# 3-CPU_SIGNAL.net
KiCad netlist of a schematic drawn in Altium Designer
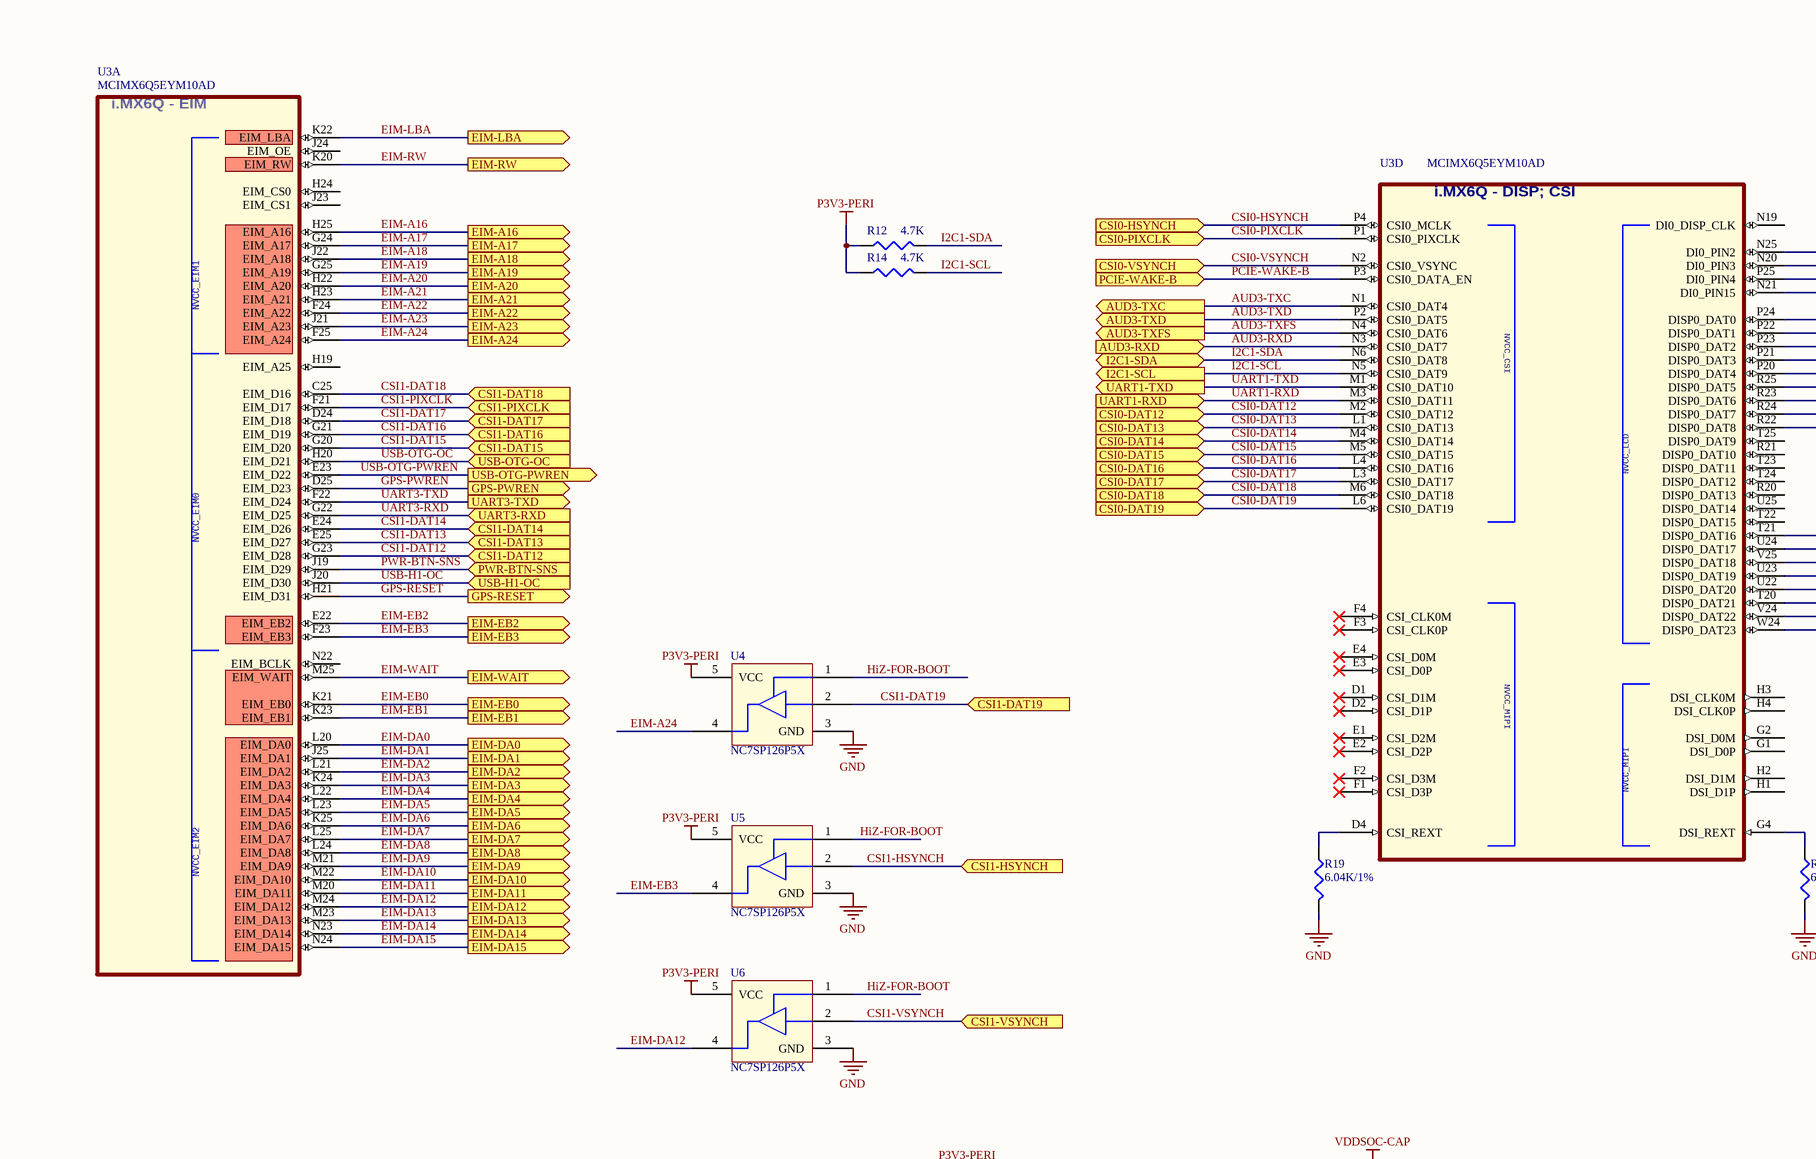
[diagram p0: 3-CPU_SIGNAL.SchDoc, top left]
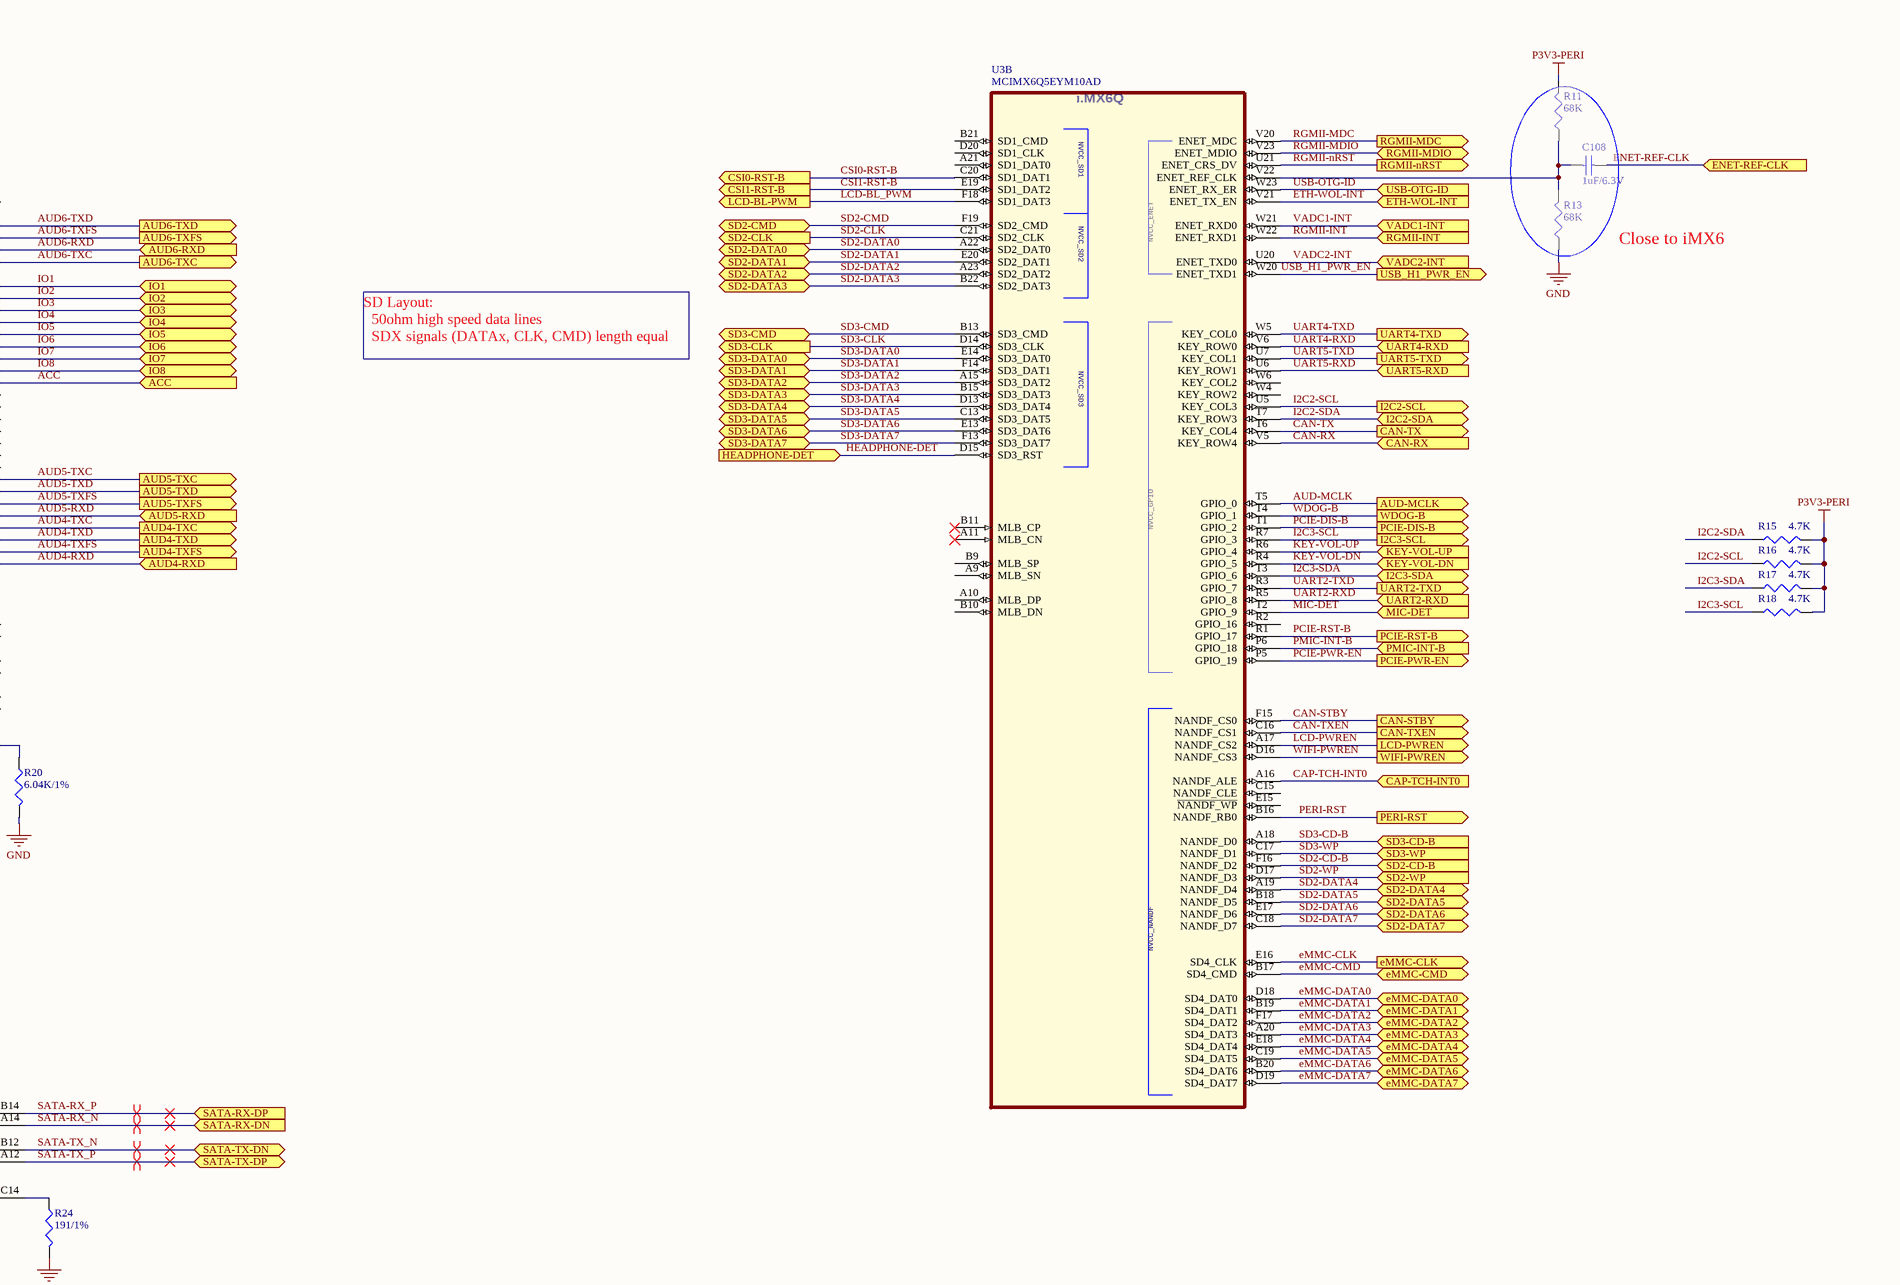
[diagram p1: 3-CPU_SIGNAL.SchDoc, top right]
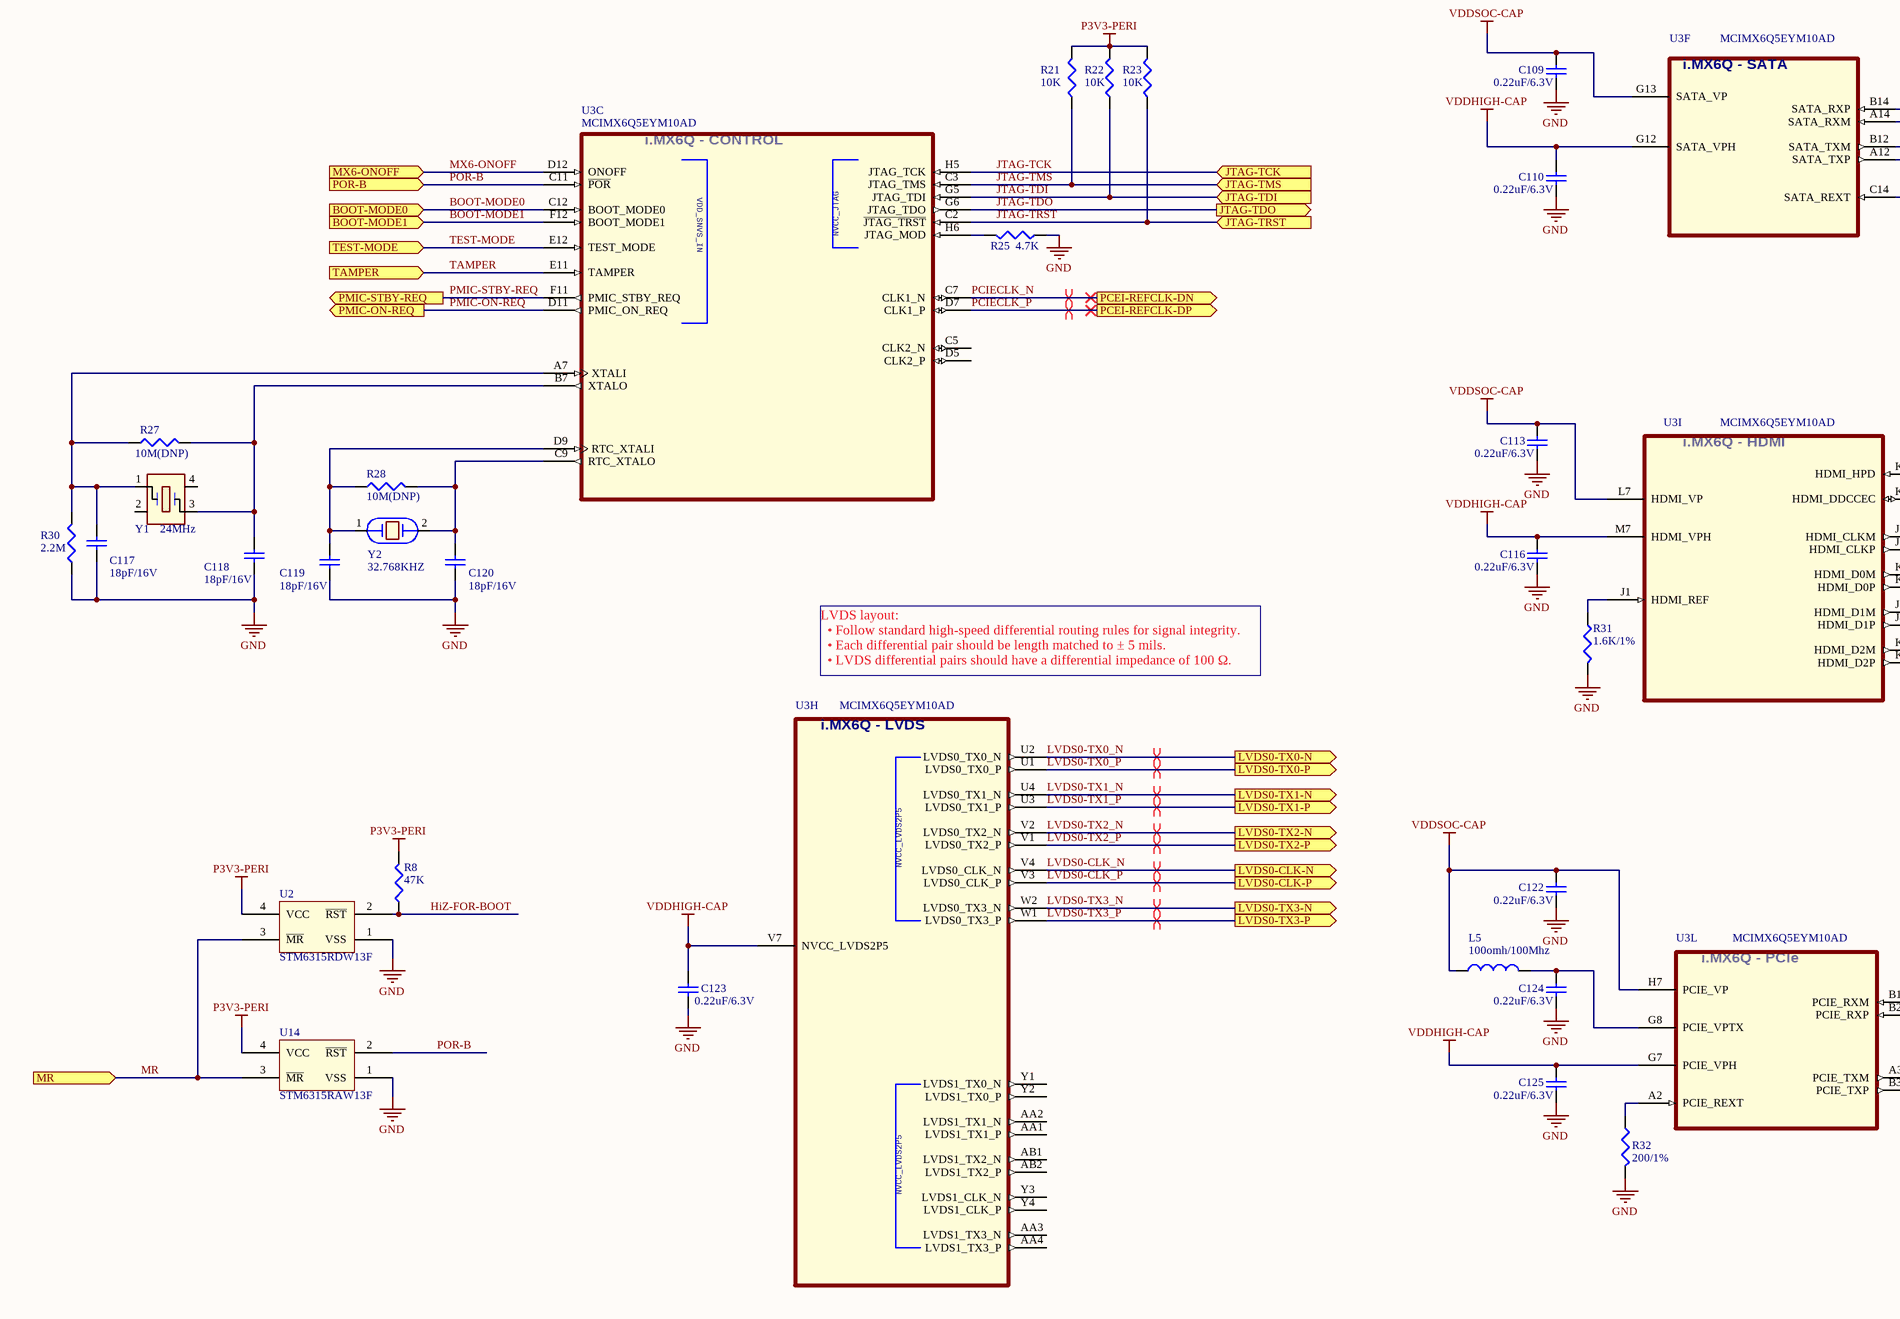
[diagram p2: 3-CPU_SIGNAL.SchDoc, bottom left]
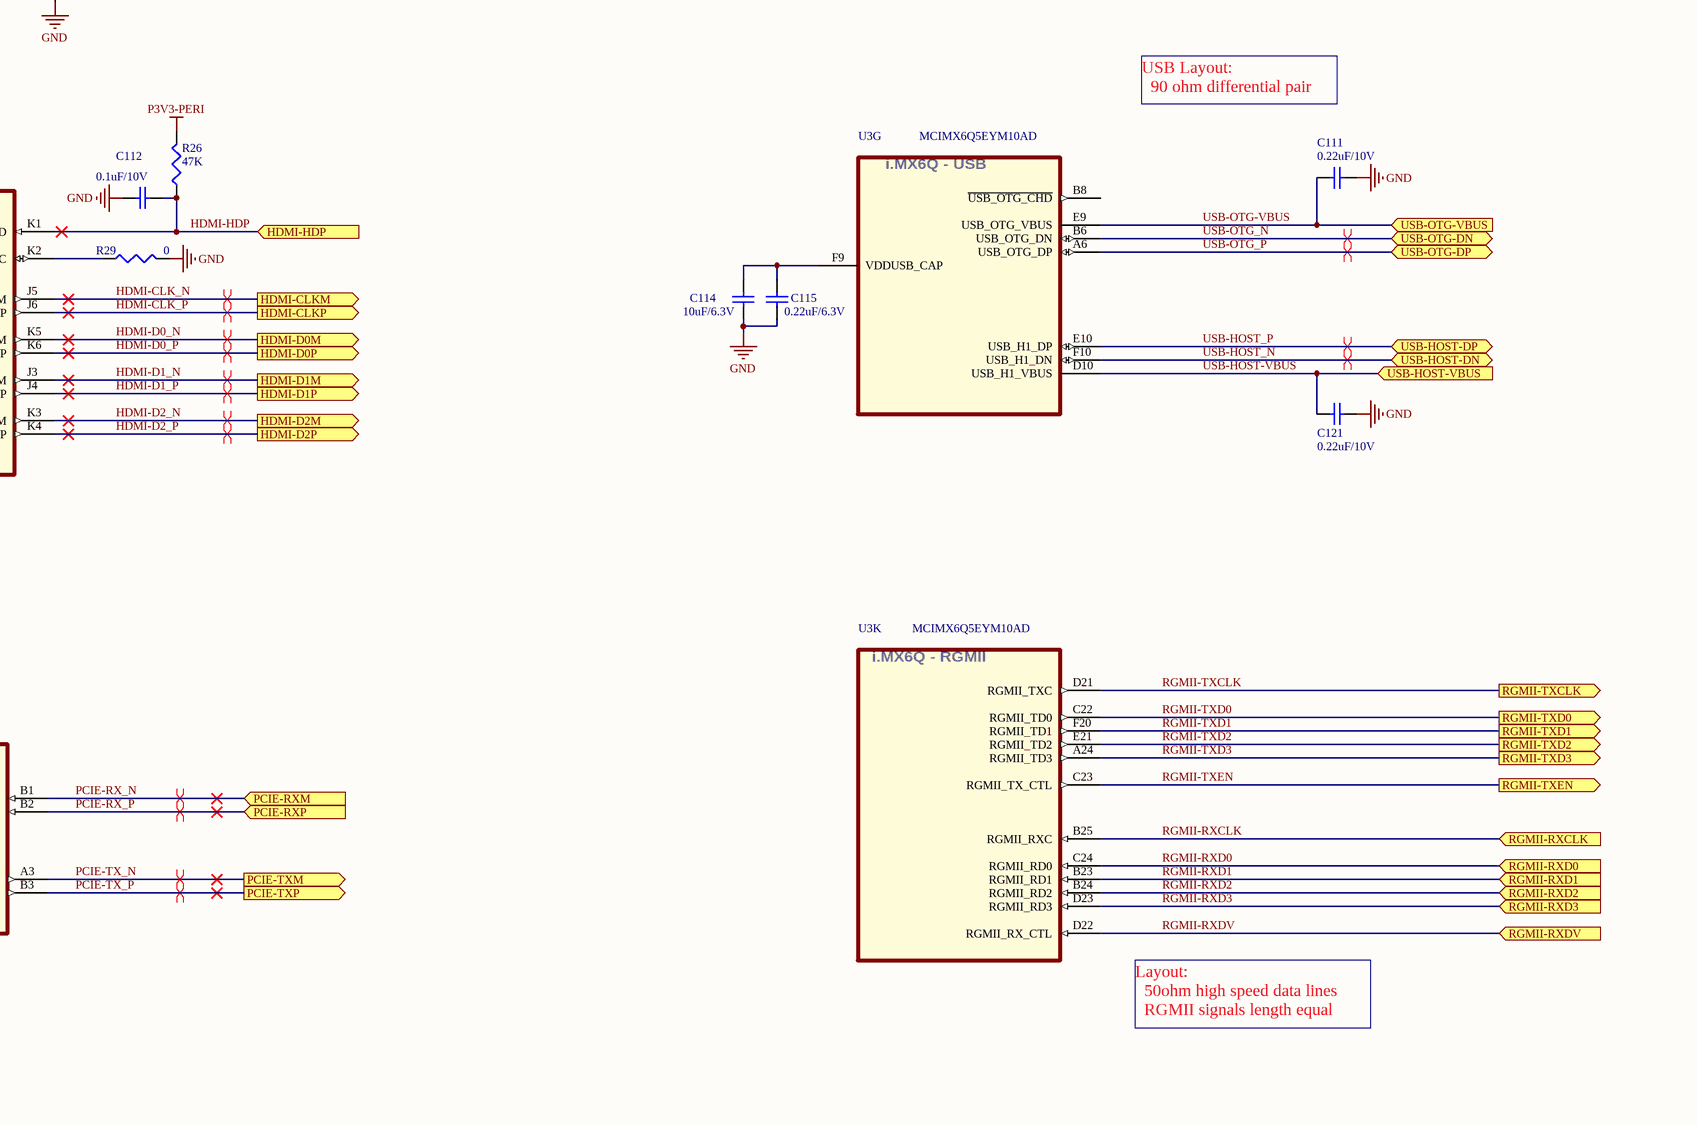
[diagram p3: 3-CPU_SIGNAL.SchDoc, bottom right]

(export (version "E")
  (design (tool "Eeschema 10.0.6"))
  (components
    (comp (ref "C108")
      (value "1uF/6.3V")
      (footprint "0402_CC")
      (description "Capacitor")
      (fields (field (name "PUBLISHER") "Altium Limited"))
      (libsource (lib "Miscellaneous Devices") (part "Cap"))
    )
    (comp (ref "C109")
      (value "0.22uF/6.3V")
      (footprint "0201_CC")
      (description "Capacitor")
      (fields (field (name "PUBLISHER") "Altium Limited"))
      (libsource (lib "Miscellaneous Devices") (part "Cap"))
    )
    (comp (ref "C110")
      (value "0.22uF/6.3V")
      (footprint "0201_CC")
      (description "Capacitor")
      (fields (field (name "PUBLISHER") "Altium Limited"))
      (libsource (lib "Miscellaneous Devices") (part "Cap"))
    )
    (comp (ref "C111")
      (value "0.22uF/10V")
      (footprint "0402_CC")
      (description "Capacitor")
      (fields (field (name "PUBLISHER") "Altium Limited"))
      (libsource (lib "Miscellaneous Devices") (part "Cap"))
    )
    (comp (ref "C112")
      (value "0.1uF/10V")
      (footprint "0402_CC")
      (description "Capacitor")
      (fields (field (name "PUBLISHER") "Altium Limited"))
      (libsource (lib "Miscellaneous Devices") (part "Cap"))
    )
    (comp (ref "C113")
      (value "0.22uF/6.3V")
      (footprint "0201_CC")
      (description "Capacitor")
      (fields (field (name "PUBLISHER") "Altium Limited"))
      (libsource (lib "Miscellaneous Devices") (part "Cap"))
    )
    (comp (ref "C114")
      (value "10uF/6.3V")
      (footprint "0805_CC")
      (description "Capacitor")
      (fields (field (name "PUBLISHER") "Altium Limited"))
      (libsource (lib "Miscellaneous Devices") (part "Cap"))
    )
    (comp (ref "C115")
      (value "0.22uF/6.3V")
      (footprint "0201_CC")
      (description "Capacitor")
      (fields (field (name "PUBLISHER") "Altium Limited"))
      (libsource (lib "Miscellaneous Devices") (part "Cap"))
    )
    (comp (ref "C116")
      (value "0.22uF/6.3V")
      (footprint "0201_CC")
      (description "Capacitor")
      (fields (field (name "PUBLISHER") "Altium Limited"))
      (libsource (lib "Miscellaneous Devices") (part "Cap"))
    )
    (comp (ref "C117")
      (value "18pF/16V")
      (footprint "0402_CC")
      (description "Capacitor")
      (fields (field (name "PUBLISHER") "Altium Limited"))
      (libsource (lib "Miscellaneous Devices") (part "Cap"))
    )
    (comp (ref "C118")
      (value "18pF/16V")
      (footprint "0402_CC")
      (description "Capacitor")
      (fields (field (name "PUBLISHER") "Altium Limited"))
      (libsource (lib "Miscellaneous Devices") (part "Cap"))
    )
    (comp (ref "C119")
      (value "18pF/16V")
      (footprint "0402_CC")
      (description "Capacitor")
      (fields (field (name "PUBLISHER") "Altium Limited"))
      (libsource (lib "Miscellaneous Devices") (part "Cap"))
    )
    (comp (ref "C120")
      (value "18pF/16V")
      (footprint "0402_CC")
      (description "Capacitor")
      (fields (field (name "PUBLISHER") "Altium Limited"))
      (libsource (lib "Miscellaneous Devices") (part "Cap"))
    )
    (comp (ref "C121")
      (value "0.22uF/10V")
      (footprint "0402_CC")
      (description "Capacitor")
      (fields (field (name "PUBLISHER") "Altium Limited"))
      (libsource (lib "Miscellaneous Devices") (part "Cap"))
    )
    (comp (ref "C122")
      (value "0.22uF/6.3V")
      (footprint "0201_CC")
      (description "Capacitor")
      (fields (field (name "PUBLISHER") "Altium Limited"))
      (libsource (lib "Miscellaneous Devices") (part "Cap"))
    )
    (comp (ref "C123")
      (value "0.22uF/6.3V")
      (footprint "0201_CC")
      (description "Capacitor")
      (fields (field (name "PUBLISHER") "Altium Limited"))
      (libsource (lib "Miscellaneous Devices") (part "Cap"))
    )
    (comp (ref "C124")
      (value "0.22uF/6.3V")
      (footprint "0201_CC")
      (description "Capacitor")
      (fields (field (name "PUBLISHER") "Altium Limited"))
      (libsource (lib "Miscellaneous Devices") (part "Cap"))
    )
    (comp (ref "C125")
      (value "0.22uF/6.3V")
      (footprint "0201_CC")
      (description "Capacitor")
      (fields (field (name "PUBLISHER") "Altium Limited"))
      (libsource (lib "Miscellaneous Devices") (part "Cap"))
    )
    (comp (ref "L5")
      (value "100omh/100Mhz")
      (footprint "0603_CC")
      (description "Inductor")
      (fields (field (name "PUBLISHER") "Altium Limited"))
      (libsource (lib "Miscellaneous Devices") (part "Inductor"))
    )
    (comp (ref "R8")
      (value "47K")
      (footprint "0402_CC")
      (description "Resistor")
      (fields (field (name "PUBLISHER") "Altium Limited"))
      (libsource (lib "Miscellaneous Devices") (part "Res3"))
    )
    (comp (ref "R11")
      (value "68K")
      (footprint "0402_CC")
      (description "Resistor")
      (fields (field (name "PUBLISHER") "Altium Limited"))
      (libsource (lib "Miscellaneous Devices") (part "Res3"))
    )
    (comp (ref "R12")
      (value "4.7K")
      (footprint "0402_CC")
      (description "Resistor")
      (fields (field (name "PUBLISHER") "Altium Limited"))
      (libsource (lib "Miscellaneous Devices") (part "Res3"))
    )
    (comp (ref "R13")
      (value "68K")
      (footprint "0402_CC")
      (description "Resistor")
      (fields (field (name "PUBLISHER") "Altium Limited"))
      (libsource (lib "Miscellaneous Devices") (part "Res3"))
    )
    (comp (ref "R14")
      (value "4.7K")
      (footprint "0402_CC")
      (description "Resistor")
      (fields (field (name "PUBLISHER") "Altium Limited"))
      (libsource (lib "Miscellaneous Devices") (part "Res3"))
    )
    (comp (ref "R15")
      (value "4.7K")
      (footprint "0402_CC")
      (description "Resistor")
      (fields (field (name "PUBLISHER") "Altium Limited"))
      (libsource (lib "Miscellaneous Devices") (part "Res3"))
    )
    (comp (ref "R16")
      (value "4.7K")
      (footprint "0402_CC")
      (description "Resistor")
      (fields (field (name "PUBLISHER") "Altium Limited"))
      (libsource (lib "Miscellaneous Devices") (part "Res3"))
    )
    (comp (ref "R17")
      (value "4.7K")
      (footprint "0402_CC")
      (description "Resistor")
      (fields (field (name "PUBLISHER") "Altium Limited"))
      (libsource (lib "Miscellaneous Devices") (part "Res3"))
    )
    (comp (ref "R18")
      (value "4.7K")
      (footprint "0402_CC")
      (description "Resistor")
      (fields (field (name "PUBLISHER") "Altium Limited"))
      (libsource (lib "Miscellaneous Devices") (part "Res3"))
    )
    (comp (ref "R19")
      (value "6.04K/1%")
      (footprint "0402_CC")
      (description "Resistor")
      (fields (field (name "PUBLISHER") "Altium Limited"))
      (libsource (lib "Miscellaneous Devices") (part "Res3"))
    )
    (comp (ref "R20")
      (value "6.04K/1%")
      (footprint "0402_CC")
      (description "Resistor")
      (fields (field (name "PUBLISHER") "Altium Limited"))
      (libsource (lib "Miscellaneous Devices") (part "Res3"))
    )
    (comp (ref "R21")
      (value "10K")
      (footprint "0402_CC")
      (description "Resistor")
      (fields (field (name "PUBLISHER") "Altium Limited"))
      (libsource (lib "Miscellaneous Devices") (part "Res3"))
    )
    (comp (ref "R22")
      (value "10K")
      (footprint "0402_CC")
      (description "Resistor")
      (fields (field (name "PUBLISHER") "Altium Limited"))
      (libsource (lib "Miscellaneous Devices") (part "Res3"))
    )
    (comp (ref "R23")
      (value "10K")
      (footprint "0402_CC")
      (description "Resistor")
      (fields (field (name "PUBLISHER") "Altium Limited"))
      (libsource (lib "Miscellaneous Devices") (part "Res3"))
    )
    (comp (ref "R24")
      (value "191/1%")
      (footprint "0402_CC")
      (description "Resistor")
      (fields (field (name "PUBLISHER") "Altium Limited"))
      (libsource (lib "Miscellaneous Devices") (part "Res3"))
    )
    (comp (ref "R25")
      (value "4.7K")
      (footprint "0402_CC")
      (description "Resistor")
      (fields (field (name "PUBLISHER") "Altium Limited"))
      (libsource (lib "Miscellaneous Devices") (part "Res3"))
    )
    (comp (ref "R26")
      (value "47K")
      (footprint "0402_CC")
      (description "Resistor")
      (fields (field (name "PUBLISHER") "Altium Limited"))
      (libsource (lib "Miscellaneous Devices") (part "Res3"))
    )
    (comp (ref "R27")
      (value "10M(DNP)")
      (footprint "0402_CC")
      (description "Resistor")
      (fields (field (name "PUBLISHER") "Altium Limited"))
      (libsource (lib "Miscellaneous Devices") (part "Res3"))
    )
    (comp (ref "R28")
      (value "10M(DNP)")
      (footprint "0402_CC")
      (description "Resistor")
      (fields (field (name "PUBLISHER") "Altium Limited"))
      (libsource (lib "Miscellaneous Devices") (part "Res3"))
    )
    (comp (ref "R29")
      (value "0")
      (footprint "0402_CC")
      (description "Resistor")
      (fields (field (name "PUBLISHER") "Altium Limited"))
      (libsource (lib "Miscellaneous Devices") (part "Res3"))
    )
    (comp (ref "R30")
      (value "2.2M")
      (footprint "0402_CC")
      (description "Resistor")
      (fields (field (name "PUBLISHER") "Altium Limited"))
      (libsource (lib "Miscellaneous Devices") (part "Res3"))
    )
    (comp (ref "R31")
      (value "1.6K/1%")
      (footprint "0402_CC")
      (description "Resistor")
      (fields (field (name "PUBLISHER") "Altium Limited"))
      (libsource (lib "Miscellaneous Devices") (part "Res3"))
    )
    (comp (ref "R32")
      (value "200/1%")
      (footprint "0402_CC")
      (description "Resistor")
      (fields (field (name "PUBLISHER") "Altium Limited"))
      (libsource (lib "Miscellaneous Devices") (part "Res3"))
    )
    (comp (ref "U2")
      (value "STM6315RDW13F")
      (footprint "SOT143-4")
      (libsource (lib "Schlib") (part "STM6315"))
    )
    (comp (ref "U3")
      (value "MCIMX6Q5EYM10AD")
      (footprint "FCPBGA")
      (description "IC MCU MX6QUAD ARM CORTEX-A9 FCPBGA624")
      (libsource (lib "*") (part "PCIMX6Q6VV1A"))
    )
    (comp (ref "U4") (value "NC7SP126P5X") (footprint "SC70") (libsource (lib "Schlib") (part "NC7SP126P5X")))
    (comp (ref "U5") (value "NC7SP126P5X") (footprint "SC70") (libsource (lib "Schlib") (part "NC7SP126P5X")))
    (comp (ref "U6") (value "NC7SP126P5X") (footprint "SC70") (libsource (lib "Schlib") (part "NC7SP126P5X")))
    (comp (ref "U14")
      (value "STM6315RAW13F")
      (footprint "SOT143-4")
      (libsource (lib "Schlib") (part "STM6315"))
    )
    (comp (ref "Y1")
      (value "24MHz")
      (footprint "XTAL4_SX_3225")
      (description "XTAL 24MHZ -- 3.2X2.5MM SMT")
      (libsource (lib "*") (part "XTAL_13Y_A"))
    )
    (comp (ref "Y2")
      (value "32.768KHZ")
      (footprint "XTAL2-3P2X1P5-SM")
      (description "XTAL 32.768KHZ 12.5PF 20PPM 3.2X1.5MM SMT")
      (libsource (lib "*") (part "XTAL"))
    )
  )
  (nets
    (net (code "1") (name "/ACC") (class "Default")
      (node (ref "U3") (pin "R22") (pinfunction "DISP0_DAT8_R22") (pintype "bidirectional"))
    )
    (net (code "2") (name "/AUD-MCLK") (class "Default")
      (node (ref "U3") (pin "T5") (pinfunction "GPIO_0_T5") (pintype "bidirectional"))
    )
    (net (code "3") (name "/AUD3-RXD") (class "Default")
      (node (ref "U3") (pin "N3") (pinfunction "CSI0_DAT7_N3") (pintype "bidirectional"))
    )
    (net (code "4") (name "/AUD3-TXC") (class "Default")
      (node (ref "U3") (pin "N1") (pinfunction "CSI0_DAT4_N1") (pintype "bidirectional"))
    )
    (net (code "5") (name "/AUD3-TXD") (class "Default")
      (node (ref "U3") (pin "P2") (pinfunction "CSI0_DAT5_P2") (pintype "bidirectional"))
    )
    (net (code "6") (name "/AUD3-TXFS") (class "Default")
      (node (ref "U3") (pin "N4") (pinfunction "CSI0_DAT6_N4") (pintype "bidirectional"))
    )
    (net (code "7") (name "/AUD4-RXD") (class "Default")
      (node (ref "U3") (pin "W24") (pinfunction "DISP0_DAT23_W24") (pintype "bidirectional"))
    )
    (net (code "8") (name "/AUD4-TXC") (class "Default")
      (node (ref "U3") (pin "U22") (pinfunction "DISP0_DAT20_U22") (pintype "bidirectional"))
    )
    (net (code "9") (name "/AUD4-TXD") (class "Default")
      (node (ref "U3") (pin "T20") (pinfunction "DISP0_DAT21_T20") (pintype "bidirectional"))
    )
    (net (code "10") (name "/AUD4-TXFS") (class "Default")
      (node (ref "U3") (pin "V24") (pinfunction "DISP0_DAT22_V24") (pintype "bidirectional"))
    )
    (net (code "11") (name "/AUD5-RXD") (class "Default")
      (node (ref "U3") (pin "U23") (pinfunction "DISP0_DAT19_U23") (pintype "bidirectional"))
    )
    (net (code "12") (name "/AUD5-TXC") (class "Default")
      (node (ref "U3") (pin "T21") (pinfunction "DISP0_DAT16_T21") (pintype "bidirectional"))
    )
    (net (code "13") (name "/AUD5-TXD") (class "Default")
      (node (ref "U3") (pin "U24") (pinfunction "DISP0_DAT17_U24") (pintype "bidirectional"))
    )
    (net (code "14") (name "/AUD5-TXFS") (class "Default")
      (node (ref "U3") (pin "V25") (pinfunction "DISP0_DAT18_V25") (pintype "bidirectional"))
    )
    (net (code "15") (name "/AUD6-RXD") (class "Default")
      (node (ref "U3") (pin "P25") (pinfunction "DI0_PIN4_P25") (pintype "bidirectional"))
    )
    (net (code "16") (name "/AUD6-TXC") (class "Default")
      (node (ref "U3") (pin "N21") (pinfunction "DI0_PIN15_N21") (pintype "bidirectional"))
    )
    (net (code "17") (name "/AUD6-TXD") (class "Default")
      (node (ref "U3") (pin "N25") (pinfunction "DI0_PIN2_N25") (pintype "bidirectional"))
    )
    (net (code "18") (name "/AUD6-TXFS") (class "Default")
      (node (ref "U3") (pin "N20") (pinfunction "DI0_PIN3_N20") (pintype "bidirectional"))
    )
    (net (code "19") (name "/BOOT-MODE0") (class "Default")
      (node (ref "U3") (pin "C12") (pinfunction "BOOT_MODE0_C12") (pintype "input"))
    )
    (net (code "20") (name "/BOOT-MODE1") (class "Default")
      (node (ref "U3") (pin "F12") (pinfunction "BOOT_MODE1_F12") (pintype "input"))
    )
    (net (code "21") (name "/CAN-RX") (class "Default")
      (node (ref "U3") (pin "V5") (pinfunction "KEY_ROW4_V5") (pintype "bidirectional"))
    )
    (net (code "22") (name "/CAN-STBY") (class "Default")
      (node (ref "U3") (pin "F15") (pinfunction "NANDF_CS0_F15") (pintype "bidirectional"))
    )
    (net (code "23") (name "/CAN-TX") (class "Default")
      (node (ref "U3") (pin "T6") (pinfunction "KEY_COL4_T6") (pintype "bidirectional"))
    )
    (net (code "24") (name "/CAN-TXEN") (class "Default")
      (node (ref "U3") (pin "C16") (pinfunction "NANDF_CS1_C16") (pintype "bidirectional"))
    )
    (net (code "25") (name "/CAP-TCH-INT0") (class "Default")
      (node (ref "U3") (pin "A16") (pinfunction "NANDF_ALE_A16") (pintype "bidirectional"))
    )
    (net (code "26") (name "/CSI0-DAT12") (class "Default")
      (node (ref "U3") (pin "M2") (pinfunction "CSI0_DAT12_M2") (pintype "bidirectional"))
    )
    (net (code "27") (name "/CSI0-DAT13") (class "Default")
      (node (ref "U3") (pin "L1") (pinfunction "CSI0_DAT13_L1") (pintype "bidirectional"))
    )
    (net (code "28") (name "/CSI0-DAT14") (class "Default")
      (node (ref "U3") (pin "M4") (pinfunction "CSI0_DAT14_M4") (pintype "bidirectional"))
    )
    (net (code "29") (name "/CSI0-DAT15") (class "Default")
      (node (ref "U3") (pin "M5") (pinfunction "CSI0_DAT15_M5") (pintype "bidirectional"))
    )
    (net (code "30") (name "/CSI0-DAT16") (class "Default")
      (node (ref "U3") (pin "L4") (pinfunction "CSI0_DAT16_L4") (pintype "bidirectional"))
    )
    (net (code "31") (name "/CSI0-DAT17") (class "Default")
      (node (ref "U3") (pin "L3") (pinfunction "CSI0_DAT17_L3") (pintype "bidirectional"))
    )
    (net (code "32") (name "/CSI0-DAT18") (class "Default")
      (node (ref "U3") (pin "M6") (pinfunction "CSI0_DAT18_M6") (pintype "bidirectional"))
    )
    (net (code "33") (name "/CSI0-DAT19") (class "Default")
      (node (ref "U3") (pin "L6") (pinfunction "CSI0_DAT19_L6") (pintype "bidirectional"))
    )
    (net (code "34") (name "/CSI0-HSYNCH") (class "Default")
      (node (ref "U3") (pin "P4") (pinfunction "CSI0_MCLK_P4") (pintype "bidirectional"))
    )
    (net (code "35") (name "/CSI0-PIXCLK") (class "Default")
      (node (ref "U3") (pin "P1") (pinfunction "CSI0_PIXCLK_P1") (pintype "bidirectional"))
    )
    (net (code "36") (name "/CSI0-RST-B") (class "Default")
      (node (ref "U3") (pin "C20") (pinfunction "SD1_DAT1_C20") (pintype "bidirectional"))
    )
    (net (code "37") (name "/CSI0-VSYNCH") (class "Default")
      (node (ref "U3") (pin "N2") (pinfunction "CSI0_VSYNC_N2") (pintype "bidirectional"))
    )
    (net (code "38") (name "/CSI1-DAT12") (class "Default")
      (node (ref "U3") (pin "G23") (pinfunction "EIM_D28_G23") (pintype "bidirectional"))
    )
    (net (code "39") (name "/CSI1-DAT13") (class "Default")
      (node (ref "U3") (pin "E25") (pinfunction "EIM_D27_E25") (pintype "bidirectional"))
    )
    (net (code "40") (name "/CSI1-DAT14") (class "Default")
      (node (ref "U3") (pin "E24") (pinfunction "EIM_D26_E24") (pintype "bidirectional"))
    )
    (net (code "41") (name "/CSI1-DAT15") (class "Default")
      (node (ref "U3") (pin "G20") (pinfunction "EIM_D20_G20") (pintype "bidirectional"))
    )
    (net (code "42") (name "/CSI1-DAT16") (class "Default")
      (node (ref "U3") (pin "G21") (pinfunction "EIM_D19_G21") (pintype "bidirectional"))
    )
    (net (code "43") (name "/CSI1-DAT17") (class "Default")
      (node (ref "U3") (pin "D24") (pinfunction "EIM_D18_D24") (pintype "bidirectional"))
    )
    (net (code "44") (name "/CSI1-DAT18") (class "Default")
      (node (ref "U3") (pin "C25") (pinfunction "EIM_D16_C25") (pintype "bidirectional"))
    )
    (net (code "45") (name "/CSI1-DAT19") (class "Default")
      (node (ref "U4") (pin "2") (pinfunction "A_2") (pintype "passive"))
    )
    (net (code "46") (name "/CSI1-HSYNCH") (class "Default")
      (node (ref "U5") (pin "2") (pinfunction "A_2") (pintype "passive"))
    )
    (net (code "47") (name "/CSI1-PIXCLK") (class "Default")
      (node (ref "U3") (pin "F21") (pinfunction "EIM_D17_F21") (pintype "bidirectional"))
    )
    (net (code "48") (name "/CSI1-RST-B") (class "Default")
      (node (ref "U3") (pin "E19") (pinfunction "SD1_DAT2_E19") (pintype "bidirectional"))
    )
    (net (code "49") (name "/CSI1-VSYNCH") (class "Default")
      (node (ref "U6") (pin "2") (pinfunction "A_2") (pintype "passive"))
    )
    (net (code "50") (name "/EIM-A16") (class "Default")
      (node (ref "U3") (pin "H25") (pinfunction "EIM_A16_H25") (pintype "bidirectional"))
    )
    (net (code "51") (name "/EIM-A17") (class "Default")
      (node (ref "U3") (pin "G24") (pinfunction "EIM_A17_G24") (pintype "bidirectional"))
    )
    (net (code "52") (name "/EIM-A18") (class "Default")
      (node (ref "U3") (pin "J22") (pinfunction "EIM_A18_J22") (pintype "bidirectional"))
    )
    (net (code "53") (name "/EIM-A19") (class "Default")
      (node (ref "U3") (pin "G25") (pinfunction "EIM_A19_G25") (pintype "bidirectional"))
    )
    (net (code "54") (name "/EIM-A20") (class "Default")
      (node (ref "U3") (pin "H22") (pinfunction "EIM_A20_H22") (pintype "bidirectional"))
    )
    (net (code "55") (name "/EIM-A21") (class "Default")
      (node (ref "U3") (pin "H23") (pinfunction "EIM_A21_H23") (pintype "bidirectional"))
    )
    (net (code "56") (name "/EIM-A22") (class "Default")
      (node (ref "U3") (pin "F24") (pinfunction "EIM_A22_F24") (pintype "bidirectional"))
    )
    (net (code "57") (name "/EIM-A23") (class "Default")
      (node (ref "U3") (pin "J21") (pinfunction "EIM_A23_J21") (pintype "bidirectional"))
    )
    (net (code "58") (name "/EIM-A24") (class "Default")
      (node (ref "U3") (pin "F25") (pinfunction "EIM_A24_F25") (pintype "bidirectional"))
      (node (ref "U4") (pin "4") (pinfunction "Y_4") (pintype "passive"))
    )
    (net (code "59") (name "/EIM-DA0") (class "Default")
      (node (ref "U3") (pin "L20") (pinfunction "EIM_DA0_L20") (pintype "bidirectional"))
    )
    (net (code "60") (name "/EIM-DA1") (class "Default")
      (node (ref "U3") (pin "J25") (pinfunction "EIM_DA1_J25") (pintype "bidirectional"))
    )
    (net (code "61") (name "/EIM-DA2") (class "Default")
      (node (ref "U3") (pin "L21") (pinfunction "EIM_DA2_L21") (pintype "bidirectional"))
    )
    (net (code "62") (name "/EIM-DA3") (class "Default")
      (node (ref "U3") (pin "K24") (pinfunction "EIM_DA3_K24") (pintype "bidirectional"))
    )
    (net (code "63") (name "/EIM-DA4") (class "Default")
      (node (ref "U3") (pin "L22") (pinfunction "EIM_DA4_L22") (pintype "bidirectional"))
    )
    (net (code "64") (name "/EIM-DA5") (class "Default")
      (node (ref "U3") (pin "L23") (pinfunction "EIM_DA5_L23") (pintype "bidirectional"))
    )
    (net (code "65") (name "/EIM-DA6") (class "Default")
      (node (ref "U3") (pin "K25") (pinfunction "EIM_DA6_K25") (pintype "bidirectional"))
    )
    (net (code "66") (name "/EIM-DA7") (class "Default")
      (node (ref "U3") (pin "L25") (pinfunction "EIM_DA7_L25") (pintype "bidirectional"))
    )
    (net (code "67") (name "/EIM-DA8") (class "Default")
      (node (ref "U3") (pin "L24") (pinfunction "EIM_DA8_L24") (pintype "bidirectional"))
    )
    (net (code "68") (name "/EIM-DA9") (class "Default")
      (node (ref "U3") (pin "M21") (pinfunction "EIM_DA9_M21") (pintype "bidirectional"))
    )
    (net (code "69") (name "/EIM-DA10") (class "Default")
      (node (ref "U3") (pin "M22") (pinfunction "EIM_DA10_M22") (pintype "bidirectional"))
    )
    (net (code "70") (name "/EIM-DA11") (class "Default")
      (node (ref "U3") (pin "M20") (pinfunction "EIM_DA11_M20") (pintype "bidirectional"))
    )
    (net (code "71") (name "/EIM-DA12") (class "Default")
      (node (ref "U3") (pin "M24") (pinfunction "EIM_DA12_M24") (pintype "bidirectional"))
      (node (ref "U6") (pin "4") (pinfunction "Y_4") (pintype "passive"))
    )
    (net (code "72") (name "/EIM-DA13") (class "Default")
      (node (ref "U3") (pin "M23") (pinfunction "EIM_DA13_M23") (pintype "bidirectional"))
    )
    (net (code "73") (name "/EIM-DA14") (class "Default")
      (node (ref "U3") (pin "N23") (pinfunction "EIM_DA14_N23") (pintype "bidirectional"))
    )
    (net (code "74") (name "/EIM-DA15") (class "Default")
      (node (ref "U3") (pin "N24") (pinfunction "EIM_DA15_N24") (pintype "bidirectional"))
    )
    (net (code "75") (name "/EIM-EB0") (class "Default")
      (node (ref "U3") (pin "K21") (pinfunction "EIM_EB0_K21") (pintype "bidirectional"))
    )
    (net (code "76") (name "/EIM-EB1") (class "Default")
      (node (ref "U3") (pin "K23") (pinfunction "EIM_EB1_K23") (pintype "bidirectional"))
    )
    (net (code "77") (name "/EIM-EB2") (class "Default")
      (node (ref "U3") (pin "E22") (pinfunction "EIM_EB2_E22") (pintype "bidirectional"))
    )
    (net (code "78") (name "/EIM-EB3") (class "Default")
      (node (ref "U3") (pin "F23") (pinfunction "EIM_EB3_F23") (pintype "bidirectional"))
      (node (ref "U5") (pin "4") (pinfunction "Y_4") (pintype "passive"))
    )
    (net (code "79") (name "/EIM-LBA") (class "Default")
      (node (ref "U3") (pin "K22") (pinfunction "EIM_LBA_K22") (pintype "bidirectional"))
    )
    (net (code "80") (name "/EIM-RW") (class "Default")
      (node (ref "U3") (pin "K20") (pinfunction "EIM_RW_K20") (pintype "bidirectional"))
    )
    (net (code "81") (name "/EIM-WAIT") (class "Default")
      (node (ref "U3") (pin "M25") (pinfunction "EIM_WAIT_M25") (pintype "bidirectional"))
    )
    (net (code "82") (name "/ENET-REF-CLK") (class "Default")
      (node (ref "C108") (pin "2") (pinfunction "2_2") (pintype "passive"))
    )
    (net (code "83") (name "/ETH-WOL-INT") (class "Default")
      (node (ref "U3") (pin "V21") (pinfunction "ENET_TX_EN_V21") (pintype "bidirectional"))
    )
    (net (code "84") (name "/GPS-PWREN") (class "Default")
      (node (ref "U3") (pin "D25") (pinfunction "EIM_D23_D25") (pintype "bidirectional"))
    )
    (net (code "85") (name "/GPS-RESET") (class "Default")
      (node (ref "U3") (pin "H21") (pinfunction "EIM_D31_H21") (pintype "bidirectional"))
    )
    (net (code "86") (name "/HDMI-CLK_N") (class "Default")
      (node (ref "U3") (pin "J5") (pinfunction "HDMI_CLKM_J5") (pintype "output"))
    )
    (net (code "87") (name "/HDMI-CLK_P") (class "Default")
      (node (ref "U3") (pin "J6") (pinfunction "HDMI_CLKP_J6") (pintype "output"))
    )
    (net (code "88") (name "/HDMI-D0_N") (class "Default")
      (node (ref "U3") (pin "K5") (pinfunction "HDMI_D0M_K5") (pintype "output"))
    )
    (net (code "89") (name "/HDMI-D0_P") (class "Default")
      (node (ref "U3") (pin "K6") (pinfunction "HDMI_D0P_K6") (pintype "output"))
    )
    (net (code "90") (name "/HDMI-D1_N") (class "Default")
      (node (ref "U3") (pin "J3") (pinfunction "HDMI_D1M_J3") (pintype "output"))
    )
    (net (code "91") (name "/HDMI-D1_P") (class "Default")
      (node (ref "U3") (pin "J4") (pinfunction "HDMI_D1P_J4") (pintype "output"))
    )
    (net (code "92") (name "/HDMI-D2_N") (class "Default")
      (node (ref "U3") (pin "K3") (pinfunction "HDMI_D2M_K3") (pintype "output"))
    )
    (net (code "93") (name "/HDMI-D2_P") (class "Default")
      (node (ref "U3") (pin "K4") (pinfunction "HDMI_D2P_K4") (pintype "output"))
    )
    (net (code "94") (name "/HDMI-HDP") (class "Default")
      (node (ref "C112") (pin "2") (pinfunction "2_2") (pintype "passive"))
      (node (ref "R26") (pin "1") (pinfunction "1_1") (pintype "passive"))
      (node (ref "U3") (pin "K1") (pinfunction "HDMI_HPD_K1") (pintype "input"))
    )
    (net (code "95") (name "/HEADPHONE-DET") (class "Default")
      (node (ref "U3") (pin "D15") (pinfunction "SD3_RST_D15") (pintype "bidirectional"))
    )
    (net (code "96") (name "/HiZ-FOR-BOOT") (class "Default")
      (node (ref "R8") (pin "1") (pinfunction "1_1") (pintype "passive"))
      (node (ref "U2") (pin "2") (pinfunction "~{RST}_2") (pintype "passive"))
      (node (ref "U4") (pin "1") (pinfunction "OE_1") (pintype "passive"))
      (node (ref "U5") (pin "1") (pinfunction "OE_1") (pintype "passive"))
      (node (ref "U6") (pin "1") (pinfunction "OE_1") (pintype "passive"))
    )
    (net (code "97") (name "/I2C1-SCL") (class "Default")
      (node (ref "R14") (pin "2") (pinfunction "2_2") (pintype "passive"))
      (node (ref "U3") (pin "N5") (pinfunction "CSI0_DAT9_N5") (pintype "bidirectional"))
    )
    (net (code "98") (name "/I2C1-SDA") (class "Default")
      (node (ref "R12") (pin "2") (pinfunction "2_2") (pintype "passive"))
      (node (ref "U3") (pin "N6") (pinfunction "CSI0_DAT8_N6") (pintype "bidirectional"))
    )
    (net (code "99") (name "/I2C2-SCL") (class "Default")
      (node (ref "R16") (pin "2") (pinfunction "2_2") (pintype "passive"))
      (node (ref "U3") (pin "U5") (pinfunction "KEY_COL3_U5") (pintype "bidirectional"))
    )
    (net (code "100") (name "/I2C2-SDA") (class "Default")
      (node (ref "R15") (pin "2") (pinfunction "2_2") (pintype "passive"))
      (node (ref "U3") (pin "T7") (pinfunction "KEY_ROW3_T7") (pintype "bidirectional"))
    )
    (net (code "101") (name "/I2C3-SCL") (class "Default")
      (node (ref "R18") (pin "2") (pinfunction "2_2") (pintype "passive"))
      (node (ref "U3") (pin "R7") (pinfunction "GPIO_3_R7") (pintype "bidirectional"))
    )
    (net (code "102") (name "/I2C3-SDA") (class "Default")
      (node (ref "R17") (pin "2") (pinfunction "2_2") (pintype "passive"))
      (node (ref "U3") (pin "T3") (pinfunction "GPIO_6_T3") (pintype "bidirectional"))
    )
    (net (code "103") (name "/IO1") (class "Default")
      (node (ref "U3") (pin "P24") (pinfunction "DISP0_DAT0_P24") (pintype "bidirectional"))
    )
    (net (code "104") (name "/IO2") (class "Default")
      (node (ref "U3") (pin "P22") (pinfunction "DISP0_DAT1_P22") (pintype "bidirectional"))
    )
    (net (code "105") (name "/IO3") (class "Default")
      (node (ref "U3") (pin "P23") (pinfunction "DISP0_DAT2_P23") (pintype "bidirectional"))
    )
    (net (code "106") (name "/IO4") (class "Default")
      (node (ref "U3") (pin "P21") (pinfunction "DISP0_DAT3_P21") (pintype "bidirectional"))
    )
    (net (code "107") (name "/IO5") (class "Default")
      (node (ref "U3") (pin "P20") (pinfunction "DISP0_DAT4_P20") (pintype "bidirectional"))
    )
    (net (code "108") (name "/IO6") (class "Default")
      (node (ref "U3") (pin "R25") (pinfunction "DISP0_DAT5_R25") (pintype "bidirectional"))
    )
    (net (code "109") (name "/IO7") (class "Default")
      (node (ref "U3") (pin "R23") (pinfunction "DISP0_DAT6_R23") (pintype "bidirectional"))
    )
    (net (code "110") (name "/IO8") (class "Default")
      (node (ref "U3") (pin "R24") (pinfunction "DISP0_DAT7_R24") (pintype "bidirectional"))
    )
    (net (code "111") (name "/JTAG-TCK") (class "Default")
      (node (ref "U3") (pin "H5") (pinfunction "JTAG_TCK_H5") (pintype "input"))
    )
    (net (code "112") (name "/JTAG-TDI") (class "Default")
      (node (ref "R22") (pin "1") (pinfunction "1_1") (pintype "passive"))
      (node (ref "U3") (pin "G5") (pinfunction "JTAG_TDI_G5") (pintype "input"))
    )
    (net (code "113") (name "/JTAG-TDO") (class "Default")
      (node (ref "U3") (pin "G6") (pinfunction "JTAG_TDO_G6") (pintype "output"))
    )
    (net (code "114") (name "/JTAG-TMS") (class "Default")
      (node (ref "R21") (pin "1") (pinfunction "1_1") (pintype "passive"))
      (node (ref "U3") (pin "C3") (pinfunction "JTAG_TMS_C3") (pintype "input"))
    )
    (net (code "115") (name "/JTAG-TRST") (class "Default")
      (node (ref "R23") (pin "1") (pinfunction "1_1") (pintype "passive"))
      (node (ref "U3") (pin "C2") (pinfunction "~{JTAG_TRST}_C2") (pintype "input"))
    )
    (net (code "116") (name "/KEY-VOL-DN") (class "Default")
      (node (ref "U3") (pin "R4") (pinfunction "GPIO_5_R4") (pintype "bidirectional"))
    )
    (net (code "117") (name "/KEY-VOL-UP") (class "Default")
      (node (ref "U3") (pin "R6") (pinfunction "GPIO_4_R6") (pintype "bidirectional"))
    )
    (net (code "118") (name "/LCD-BL_PWM") (class "Default")
      (node (ref "U3") (pin "F18") (pinfunction "SD1_DAT3_F18") (pintype "bidirectional"))
    )
    (net (code "119") (name "/LCD-PWREN") (class "Default")
      (node (ref "U3") (pin "A17") (pinfunction "NANDF_CS2_A17") (pintype "bidirectional"))
    )
    (net (code "120") (name "/LVDS0-CLK_N") (class "Default")
      (node (ref "U3") (pin "V4") (pinfunction "LVDS0_CLK_N_V4") (pintype "output"))
    )
    (net (code "121") (name "/LVDS0-CLK_P") (class "Default")
      (node (ref "U3") (pin "V3") (pinfunction "LVDS0_CLK_P_V3") (pintype "output"))
    )
    (net (code "122") (name "/LVDS0-TX0_N") (class "Default")
      (node (ref "U3") (pin "U2") (pinfunction "LVDS0_TX0_N_U2") (pintype "output"))
    )
    (net (code "123") (name "/LVDS0-TX0_P") (class "Default")
      (node (ref "U3") (pin "U1") (pinfunction "LVDS0_TX0_P_U1") (pintype "output"))
    )
    (net (code "124") (name "/LVDS0-TX1_N") (class "Default")
      (node (ref "U3") (pin "U4") (pinfunction "LVDS0_TX1_N_U4") (pintype "output"))
    )
    (net (code "125") (name "/LVDS0-TX1_P") (class "Default")
      (node (ref "U3") (pin "U3") (pinfunction "LVDS0_TX1_P_U3") (pintype "output"))
    )
    (net (code "126") (name "/LVDS0-TX2_N") (class "Default")
      (node (ref "U3") (pin "V2") (pinfunction "LVDS0_TX2_N_V2") (pintype "output"))
    )
    (net (code "127") (name "/LVDS0-TX2_P") (class "Default")
      (node (ref "U3") (pin "V1") (pinfunction "LVDS0_TX2_P_V1") (pintype "output"))
    )
    (net (code "128") (name "/LVDS0-TX3_N") (class "Default")
      (node (ref "U3") (pin "W2") (pinfunction "LVDS0_TX3_N_W2") (pintype "output"))
    )
    (net (code "129") (name "/LVDS0-TX3_P") (class "Default")
      (node (ref "U3") (pin "W1") (pinfunction "LVDS0_TX3_P_W1") (pintype "output"))
    )
    (net (code "130") (name "/MIC-DET") (class "Default")
      (node (ref "U3") (pin "T2") (pinfunction "GPIO_9_T2") (pintype "bidirectional"))
    )
    (net (code "131") (name "/MR") (class "Default")
      (node (ref "U14") (pin "3") (pinfunction "~{MR}_3") (pintype "passive"))
      (node (ref "U2") (pin "3") (pinfunction "~{MR}_3") (pintype "passive"))
    )
    (net (code "132") (name "/MX6-ONOFF") (class "Default")
      (node (ref "U3") (pin "D12") (pinfunction "ONOFF_D12") (pintype "input"))
    )
    (net (code "133") (name "/PCIE-DIS-B") (class "Default")
      (node (ref "U3") (pin "T1") (pinfunction "GPIO_2_T1") (pintype "bidirectional"))
    )
    (net (code "134") (name "/PCIE-PWR-EN") (class "Default")
      (node (ref "U3") (pin "P5") (pinfunction "GPIO_19_P5") (pintype "bidirectional"))
    )
    (net (code "135") (name "/PCIE-RST-B") (class "Default")
      (node (ref "U3") (pin "R1") (pinfunction "GPIO_17_R1") (pintype "bidirectional"))
    )
    (net (code "136") (name "/PCIE-RX_N") (class "Default")
      (node (ref "U3") (pin "B1") (pinfunction "PCIE_RXM_B1") (pintype "input"))
    )
    (net (code "137") (name "/PCIE-RX_P") (class "Default")
      (node (ref "U3") (pin "B2") (pinfunction "PCIE_RXP_B2") (pintype "input"))
    )
    (net (code "138") (name "/PCIE-TX_N") (class "Default")
      (node (ref "U3") (pin "A3") (pinfunction "PCIE_TXM_A3") (pintype "output"))
    )
    (net (code "139") (name "/PCIE-TX_P") (class "Default")
      (node (ref "U3") (pin "B3") (pinfunction "PCIE_TXP_B3") (pintype "output"))
    )
    (net (code "140") (name "/PCIE-WAKE-B") (class "Default")
      (node (ref "U3") (pin "P3") (pinfunction "CSI0_DATA_EN_P3") (pintype "bidirectional"))
    )
    (net (code "141") (name "/PCIECLK_N") (class "Default")
      (node (ref "U3") (pin "C7") (pinfunction "CLK1_N_C7") (pintype "bidirectional"))
    )
    (net (code "142") (name "/PCIECLK_P") (class "Default")
      (node (ref "U3") (pin "D7") (pinfunction "CLK1_P_D7") (pintype "bidirectional"))
    )
    (net (code "143") (name "/PERI-RST") (class "Default")
      (node (ref "U3") (pin "B16") (pinfunction "NANDF_RB0_B16") (pintype "bidirectional"))
    )
    (net (code "144") (name "/PMIC-INT-B") (class "Default")
      (node (ref "U3") (pin "P6") (pinfunction "GPIO_18_P6") (pintype "bidirectional"))
    )
    (net (code "145") (name "/PMIC-ON-REQ") (class "Default")
      (node (ref "U3") (pin "D11") (pinfunction "PMIC_ON_REQ_D11") (pintype "output"))
    )
    (net (code "146") (name "/PMIC-STBY-REQ") (class "Default")
      (node (ref "U3") (pin "F11") (pinfunction "PMIC_STBY_REQ_F11") (pintype "output"))
    )
    (net (code "147") (name "/POR-B") (class "Default")
      (node (ref "U14") (pin "2") (pinfunction "~{RST}_2") (pintype "passive"))
      (node (ref "U3") (pin "C11") (pinfunction "~{POR}_C11") (pintype "input"))
    )
    (net (code "148") (name "/PWR-BTN-SNS") (class "Default")
      (node (ref "U3") (pin "J19") (pinfunction "EIM_D29_J19") (pintype "bidirectional"))
    )
    (net (code "149") (name "/RGMII-INT") (class "Default")
      (node (ref "U3") (pin "W22") (pinfunction "ENET_RXD1_W22") (pintype "bidirectional"))
    )
    (net (code "150") (name "/RGMII-MDC") (class "Default")
      (node (ref "U3") (pin "V20") (pinfunction "ENET_MDC_V20") (pintype "bidirectional"))
    )
    (net (code "151") (name "/RGMII-MDIO") (class "Default")
      (node (ref "U3") (pin "V23") (pinfunction "ENET_MDIO_V23") (pintype "bidirectional"))
    )
    (net (code "152") (name "/RGMII-RXCLK") (class "Default")
      (node (ref "U3") (pin "B25") (pinfunction "RGMII_RXC_B25") (pintype "input"))
    )
    (net (code "153") (name "/RGMII-RXD0") (class "Default")
      (node (ref "U3") (pin "C24") (pinfunction "RGMII_RD0_C24") (pintype "input"))
    )
    (net (code "154") (name "/RGMII-RXD1") (class "Default")
      (node (ref "U3") (pin "B23") (pinfunction "RGMII_RD1_B23") (pintype "input"))
    )
    (net (code "155") (name "/RGMII-RXD2") (class "Default")
      (node (ref "U3") (pin "B24") (pinfunction "RGMII_RD2_B24") (pintype "input"))
    )
    (net (code "156") (name "/RGMII-RXD3") (class "Default")
      (node (ref "U3") (pin "D23") (pinfunction "RGMII_RD3_D23") (pintype "input"))
    )
    (net (code "157") (name "/RGMII-RXDV") (class "Default")
      (node (ref "U3") (pin "D22") (pinfunction "RGMII_RX_CTL_D22") (pintype "input"))
    )
    (net (code "158") (name "/RGMII-TXCLK") (class "Default")
      (node (ref "U3") (pin "D21") (pinfunction "RGMII_TXC_D21") (pintype "output"))
    )
    (net (code "159") (name "/RGMII-TXD0") (class "Default")
      (node (ref "U3") (pin "C22") (pinfunction "RGMII_TD0_C22") (pintype "output"))
    )
    (net (code "160") (name "/RGMII-TXD1") (class "Default")
      (node (ref "U3") (pin "F20") (pinfunction "RGMII_TD1_F20") (pintype "output"))
    )
    (net (code "161") (name "/RGMII-TXD2") (class "Default")
      (node (ref "U3") (pin "E21") (pinfunction "RGMII_TD2_E21") (pintype "output"))
    )
    (net (code "162") (name "/RGMII-TXD3") (class "Default")
      (node (ref "U3") (pin "A24") (pinfunction "RGMII_TD3_A24") (pintype "output"))
    )
    (net (code "163") (name "/RGMII-TXEN") (class "Default")
      (node (ref "U3") (pin "C23") (pinfunction "RGMII_TX_CTL_C23") (pintype "output"))
    )
    (net (code "164") (name "/RGMII-nRST") (class "Default")
      (node (ref "U3") (pin "U21") (pinfunction "ENET_CRS_DV_U21") (pintype "bidirectional"))
    )
    (net (code "165") (name "/SATA-RX_N") (class "Default")
      (node (ref "U3") (pin "A14") (pinfunction "SATA_RXM_A14") (pintype "input"))
    )
    (net (code "166") (name "/SATA-RX_P") (class "Default")
      (node (ref "U3") (pin "B14") (pinfunction "SATA_RXP_B14") (pintype "input"))
    )
    (net (code "167") (name "/SATA-TX_N") (class "Default")
      (node (ref "U3") (pin "B12") (pinfunction "SATA_TXM_B12") (pintype "output"))
    )
    (net (code "168") (name "/SATA-TX_P") (class "Default")
      (node (ref "U3") (pin "A12") (pinfunction "SATA_TXP_A12") (pintype "output"))
    )
    (net (code "169") (name "/SD2-CD-B") (class "Default")
      (node (ref "U3") (pin "F16") (pinfunction "NANDF_D2_F16") (pintype "bidirectional"))
    )
    (net (code "170") (name "/SD2-CLK") (class "Default")
      (node (ref "U3") (pin "C21") (pinfunction "SD2_CLK_C21") (pintype "bidirectional"))
    )
    (net (code "171") (name "/SD2-CMD") (class "Default")
      (node (ref "U3") (pin "F19") (pinfunction "SD2_CMD_F19") (pintype "bidirectional"))
    )
    (net (code "172") (name "/SD2-DATA0") (class "Default")
      (node (ref "U3") (pin "A22") (pinfunction "SD2_DAT0_A22") (pintype "bidirectional"))
    )
    (net (code "173") (name "/SD2-DATA1") (class "Default")
      (node (ref "U3") (pin "E20") (pinfunction "SD2_DAT1_E20") (pintype "bidirectional"))
    )
    (net (code "174") (name "/SD2-DATA2") (class "Default")
      (node (ref "U3") (pin "A23") (pinfunction "SD2_DAT2_A23") (pintype "bidirectional"))
    )
    (net (code "175") (name "/SD2-DATA3") (class "Default")
      (node (ref "U3") (pin "B22") (pinfunction "SD2_DAT3_B22") (pintype "bidirectional"))
    )
    (net (code "176") (name "/SD2-DATA4") (class "Default")
      (node (ref "U3") (pin "A19") (pinfunction "NANDF_D4_A19") (pintype "bidirectional"))
    )
    (net (code "177") (name "/SD2-DATA5") (class "Default")
      (node (ref "U3") (pin "B18") (pinfunction "NANDF_D5_B18") (pintype "bidirectional"))
    )
    (net (code "178") (name "/SD2-DATA6") (class "Default")
      (node (ref "U3") (pin "E17") (pinfunction "NANDF_D6_E17") (pintype "bidirectional"))
    )
    (net (code "179") (name "/SD2-DATA7") (class "Default")
      (node (ref "U3") (pin "C18") (pinfunction "NANDF_D7_C18") (pintype "bidirectional"))
    )
    (net (code "180") (name "/SD2-WP") (class "Default")
      (node (ref "U3") (pin "D17") (pinfunction "NANDF_D3_D17") (pintype "bidirectional"))
    )
    (net (code "181") (name "/SD3-CD-B") (class "Default")
      (node (ref "U3") (pin "A18") (pinfunction "NANDF_D0_A18") (pintype "bidirectional"))
    )
    (net (code "182") (name "/SD3-CLK") (class "Default")
      (node (ref "U3") (pin "D14") (pinfunction "SD3_CLK_D14") (pintype "bidirectional"))
    )
    (net (code "183") (name "/SD3-CMD") (class "Default")
      (node (ref "U3") (pin "B13") (pinfunction "SD3_CMD_B13") (pintype "bidirectional"))
    )
    (net (code "184") (name "/SD3-DATA0") (class "Default")
      (node (ref "U3") (pin "E14") (pinfunction "SD3_DAT0_E14") (pintype "bidirectional"))
    )
    (net (code "185") (name "/SD3-DATA1") (class "Default")
      (node (ref "U3") (pin "F14") (pinfunction "SD3_DAT1_F14") (pintype "bidirectional"))
    )
    (net (code "186") (name "/SD3-DATA2") (class "Default")
      (node (ref "U3") (pin "A15") (pinfunction "SD3_DAT2_A15") (pintype "bidirectional"))
    )
    (net (code "187") (name "/SD3-DATA3") (class "Default")
      (node (ref "U3") (pin "B15") (pinfunction "SD3_DAT3_B15") (pintype "bidirectional"))
    )
    (net (code "188") (name "/SD3-DATA4") (class "Default")
      (node (ref "U3") (pin "D13") (pinfunction "SD3_DAT4_D13") (pintype "bidirectional"))
    )
    (net (code "189") (name "/SD3-DATA5") (class "Default")
      (node (ref "U3") (pin "C13") (pinfunction "SD3_DAT5_C13") (pintype "bidirectional"))
    )
    (net (code "190") (name "/SD3-DATA6") (class "Default")
      (node (ref "U3") (pin "E13") (pinfunction "SD3_DAT6_E13") (pintype "bidirectional"))
    )
    (net (code "191") (name "/SD3-DATA7") (class "Default")
      (node (ref "U3") (pin "F13") (pinfunction "SD3_DAT7_F13") (pintype "bidirectional"))
    )
    (net (code "192") (name "/SD3-WP") (class "Default")
      (node (ref "U3") (pin "C17") (pinfunction "NANDF_D1_C17") (pintype "bidirectional"))
    )
    (net (code "193") (name "/TAMPER") (class "Default")
      (node (ref "U3") (pin "E11") (pinfunction "TAMPER_E11") (pintype "input"))
    )
    (net (code "194") (name "/TEST-MODE") (class "Default")
      (node (ref "U3") (pin "E12") (pinfunction "TEST_MODE_E12") (pintype "input"))
    )
    (net (code "195") (name "/UART1-RXD") (class "Default")
      (node (ref "U3") (pin "M3") (pinfunction "CSI0_DAT11_M3") (pintype "bidirectional"))
    )
    (net (code "196") (name "/UART1-TXD") (class "Default")
      (node (ref "U3") (pin "M1") (pinfunction "CSI0_DAT10_M1") (pintype "bidirectional"))
    )
    (net (code "197") (name "/UART2-RXD") (class "Default")
      (node (ref "U3") (pin "R5") (pinfunction "GPIO_8_R5") (pintype "bidirectional"))
    )
    (net (code "198") (name "/UART2-TXD") (class "Default")
      (node (ref "U3") (pin "R3") (pinfunction "GPIO_7_R3") (pintype "bidirectional"))
    )
    (net (code "199") (name "/UART3-RXD") (class "Default")
      (node (ref "U3") (pin "G22") (pinfunction "EIM_D25_G22") (pintype "bidirectional"))
    )
    (net (code "200") (name "/UART3-TXD") (class "Default")
      (node (ref "U3") (pin "F22") (pinfunction "EIM_D24_F22") (pintype "bidirectional"))
    )
    (net (code "201") (name "/UART4-RXD") (class "Default")
      (node (ref "U3") (pin "V6") (pinfunction "KEY_ROW0_V6") (pintype "bidirectional"))
    )
    (net (code "202") (name "/UART4-TXD") (class "Default")
      (node (ref "U3") (pin "W5") (pinfunction "KEY_COL0_W5") (pintype "bidirectional"))
    )
    (net (code "203") (name "/UART5-RXD") (class "Default")
      (node (ref "U3") (pin "U6") (pinfunction "KEY_ROW1_U6") (pintype "bidirectional"))
    )
    (net (code "204") (name "/UART5-TXD") (class "Default")
      (node (ref "U3") (pin "U7") (pinfunction "KEY_COL1_U7") (pintype "bidirectional"))
    )
    (net (code "205") (name "/USB-H1-OC") (class "Default")
      (node (ref "U3") (pin "J20") (pinfunction "EIM_D30_J20") (pintype "bidirectional"))
    )
    (net (code "206") (name "/USB-HOST-VBUS") (class "Default")
      (node (ref "C121") (pin "1") (pinfunction "1_1") (pintype "passive"))
      (node (ref "U3") (pin "D10") (pinfunction "USB_H1_VBUS_D10") (pintype "power_in"))
    )
    (net (code "207") (name "/USB-HOST_N") (class "Default")
      (node (ref "U3") (pin "F10") (pinfunction "USB_H1_DN_F10") (pintype "bidirectional"))
    )
    (net (code "208") (name "/USB-HOST_P") (class "Default")
      (node (ref "U3") (pin "E10") (pinfunction "USB_H1_DP_E10") (pintype "bidirectional"))
    )
    (net (code "209") (name "/USB-OTG-ID") (class "Default")
      (node (ref "U3") (pin "W23") (pinfunction "ENET_RX_ER_W23") (pintype "bidirectional"))
    )
    (net (code "210") (name "/USB-OTG-OC") (class "Default")
      (node (ref "U3") (pin "H20") (pinfunction "EIM_D21_H20") (pintype "bidirectional"))
    )
    (net (code "211") (name "/USB-OTG-PWREN") (class "Default")
      (node (ref "U3") (pin "E23") (pinfunction "EIM_D22_E23") (pintype "bidirectional"))
    )
    (net (code "212") (name "/USB-OTG-VBUS") (class "Default")
      (node (ref "C111") (pin "1") (pinfunction "1_1") (pintype "passive"))
      (node (ref "U3") (pin "E9") (pinfunction "USB_OTG_VBUS_E9") (pintype "power_in"))
    )
    (net (code "213") (name "/USB-OTG_N") (class "Default")
      (node (ref "U3") (pin "B6") (pinfunction "USB_OTG_DN_B6") (pintype "bidirectional"))
    )
    (net (code "214") (name "/USB-OTG_P") (class "Default")
      (node (ref "U3") (pin "A6") (pinfunction "USB_OTG_DP_A6") (pintype "bidirectional"))
    )
    (net (code "215") (name "/USB_H1_PWR_EN") (class "Default")
      (node (ref "U3") (pin "W20") (pinfunction "ENET_TXD1_W20") (pintype "bidirectional"))
    )
    (net (code "216") (name "/VADC1-INT") (class "Default")
      (node (ref "U3") (pin "W21") (pinfunction "ENET_RXD0_W21") (pintype "bidirectional"))
    )
    (net (code "217") (name "/VADC2-INT") (class "Default")
      (node (ref "U3") (pin "U20") (pinfunction "ENET_TXD0_U20") (pintype "bidirectional"))
    )
    (net (code "218") (name "/WDOG-B") (class "Default")
      (node (ref "U3") (pin "T4") (pinfunction "GPIO_1_T4") (pintype "bidirectional"))
    )
    (net (code "219") (name "/WIFI-PWREN") (class "Default")
      (node (ref "U3") (pin "D16") (pinfunction "NANDF_CS3_D16") (pintype "bidirectional"))
    )
    (net (code "220") (name "/eMMC-CLK") (class "Default")
      (node (ref "U3") (pin "E16") (pinfunction "SD4_CLK_E16") (pintype "bidirectional"))
    )
    (net (code "221") (name "/eMMC-CMD") (class "Default")
      (node (ref "U3") (pin "B17") (pinfunction "SD4_CMD_B17") (pintype "bidirectional"))
    )
    (net (code "222") (name "/eMMC-DATA0") (class "Default")
      (node (ref "U3") (pin "D18") (pinfunction "SD4_DAT0_D18") (pintype "bidirectional"))
    )
    (net (code "223") (name "/eMMC-DATA1") (class "Default")
      (node (ref "U3") (pin "B19") (pinfunction "SD4_DAT1_B19") (pintype "bidirectional"))
    )
    (net (code "224") (name "/eMMC-DATA2") (class "Default")
      (node (ref "U3") (pin "F17") (pinfunction "SD4_DAT2_F17") (pintype "bidirectional"))
    )
    (net (code "225") (name "/eMMC-DATA3") (class "Default")
      (node (ref "U3") (pin "A20") (pinfunction "SD4_DAT3_A20") (pintype "bidirectional"))
    )
    (net (code "226") (name "/eMMC-DATA4") (class "Default")
      (node (ref "U3") (pin "E18") (pinfunction "SD4_DAT4_E18") (pintype "bidirectional"))
    )
    (net (code "227") (name "/eMMC-DATA5") (class "Default")
      (node (ref "U3") (pin "C19") (pinfunction "SD4_DAT5_C19") (pintype "bidirectional"))
    )
    (net (code "228") (name "/eMMC-DATA6") (class "Default")
      (node (ref "U3") (pin "B20") (pinfunction "SD4_DAT6_B20") (pintype "bidirectional"))
    )
    (net (code "229") (name "/eMMC-DATA7") (class "Default")
      (node (ref "U3") (pin "D19") (pinfunction "SD4_DAT7_D19") (pintype "bidirectional"))
    )
    (net (code "230") (name "GND") (class "Default")
      (node (ref "C109") (pin "2") (pinfunction "2_2") (pintype "passive"))
      (node (ref "C110") (pin "2") (pinfunction "2_2") (pintype "passive"))
      (node (ref "C111") (pin "2") (pinfunction "2_2") (pintype "passive"))
      (node (ref "C112") (pin "1") (pinfunction "1_1") (pintype "passive"))
      (node (ref "C113") (pin "2") (pinfunction "2_2") (pintype "passive"))
      (node (ref "C114") (pin "2") (pinfunction "2_2") (pintype "passive"))
      (node (ref "C115") (pin "2") (pinfunction "2_2") (pintype "passive"))
      (node (ref "C116") (pin "2") (pinfunction "2_2") (pintype "passive"))
      (node (ref "C117") (pin "2") (pinfunction "2_2") (pintype "passive"))
      (node (ref "C118") (pin "2") (pinfunction "2_2") (pintype "passive"))
      (node (ref "C119") (pin "2") (pinfunction "2_2") (pintype "passive"))
      (node (ref "C120") (pin "2") (pinfunction "2_2") (pintype "passive"))
      (node (ref "C121") (pin "2") (pinfunction "2_2") (pintype "passive"))
      (node (ref "C122") (pin "2") (pinfunction "2_2") (pintype "passive"))
      (node (ref "C123") (pin "2") (pinfunction "2_2") (pintype "passive"))
      (node (ref "C124") (pin "2") (pinfunction "2_2") (pintype "passive"))
      (node (ref "C125") (pin "2") (pinfunction "2_2") (pintype "passive"))
      (node (ref "R13") (pin "2") (pinfunction "2_2") (pintype "passive"))
      (node (ref "R19") (pin "2") (pinfunction "2_2") (pintype "passive"))
      (node (ref "R20") (pin "2") (pinfunction "2_2") (pintype "passive"))
      (node (ref "R24") (pin "2") (pinfunction "2_2") (pintype "passive"))
      (node (ref "R25") (pin "1") (pinfunction "1_1") (pintype "passive"))
      (node (ref "R29") (pin "2") (pinfunction "2_2") (pintype "passive"))
      (node (ref "R30") (pin "1") (pinfunction "1_1") (pintype "passive"))
      (node (ref "R31") (pin "2") (pinfunction "2_2") (pintype "passive"))
      (node (ref "R32") (pin "2") (pinfunction "2_2") (pintype "passive"))
      (node (ref "U14") (pin "1") (pinfunction "VSS_1") (pintype "passive"))
      (node (ref "U2") (pin "1") (pinfunction "VSS_1") (pintype "passive"))
      (node (ref "U4") (pin "3") (pinfunction "GND_3") (pintype "passive"))
      (node (ref "U5") (pin "3") (pinfunction "GND_3") (pintype "passive"))
      (node (ref "U6") (pin "3") (pinfunction "GND_3") (pintype "passive"))
    )
    (net (code "231") (name "Net-(U3B-ENET_REF_CLK)") (class "Default")
      (node (ref "C108") (pin "1") (pinfunction "1_1") (pintype "passive"))
      (node (ref "R11") (pin "2") (pinfunction "2_2") (pintype "passive"))
      (node (ref "R13") (pin "1") (pinfunction "1_1") (pintype "passive"))
      (node (ref "U3") (pin "V22") (pinfunction "ENET_REF_CLK_V22") (pintype "bidirectional"))
    )
    (net (code "232") (name "Net-(U3C-JTAG_MOD)") (class "Default")
      (node (ref "R25") (pin "2") (pinfunction "2_2") (pintype "passive"))
      (node (ref "U3") (pin "H6") (pinfunction "JTAG_MOD_H6") (pintype "input"))
    )
    (net (code "233") (name "Net-(U3C-RTC_XTALI)") (class "Default")
      (node (ref "C119") (pin "1") (pinfunction "1_1") (pintype "passive"))
      (node (ref "R28") (pin "1") (pinfunction "1_1") (pintype "passive"))
      (node (ref "U3") (pin "D9") (pinfunction "RTC_XTALI_D9") (pintype "input"))
      (node (ref "Y2") (pin "1") (pinfunction "1_1") (pintype "passive"))
    )
    (net (code "234") (name "Net-(U3C-RTC_XTALO)") (class "Default")
      (node (ref "C120") (pin "1") (pinfunction "1_1") (pintype "passive"))
      (node (ref "R28") (pin "2") (pinfunction "2_2") (pintype "passive"))
      (node (ref "U3") (pin "C9") (pinfunction "RTC_XTALO_C9") (pintype "output"))
      (node (ref "Y2") (pin "2") (pinfunction "2_2") (pintype "passive"))
    )
    (net (code "235") (name "Net-(U3C-XTALI)") (class "Default")
      (node (ref "C117") (pin "1") (pinfunction "1_1") (pintype "passive"))
      (node (ref "R27") (pin "1") (pinfunction "1_1") (pintype "passive"))
      (node (ref "R30") (pin "2") (pinfunction "2_2") (pintype "passive"))
      (node (ref "U3") (pin "A7") (pinfunction "XTALI_A7") (pintype "input"))
      (node (ref "Y1") (pin "1") (pinfunction "1_1") (pintype "passive"))
    )
    (net (code "236") (name "Net-(U3C-XTALO)") (class "Default")
      (node (ref "C118") (pin "1") (pinfunction "1_1") (pintype "passive"))
      (node (ref "R27") (pin "2") (pinfunction "2_2") (pintype "passive"))
      (node (ref "U3") (pin "B7") (pinfunction "XTALO_B7") (pintype "output"))
      (node (ref "Y1") (pin "3") (pinfunction "3_3") (pintype "passive"))
    )
    (net (code "237") (name "Net-(U3D-CSI_REXT)") (class "Default")
      (node (ref "R19") (pin "1") (pinfunction "1_1") (pintype "passive"))
      (node (ref "U3") (pin "D4") (pinfunction "CSI_REXT_D4") (pintype "input"))
    )
    (net (code "238") (name "Net-(U3D-DSI_REXT)") (class "Default")
      (node (ref "R20") (pin "1") (pinfunction "1_1") (pintype "passive"))
      (node (ref "U3") (pin "G4") (pinfunction "DSI_REXT_G4") (pintype "input"))
    )
    (net (code "239") (name "Net-(U3F-SATA_REXT)") (class "Default")
      (node (ref "R24") (pin "1") (pinfunction "1_1") (pintype "passive"))
      (node (ref "U3") (pin "C14") (pinfunction "SATA_REXT_C14") (pintype "input"))
    )
    (net (code "240") (name "Net-(U3G-VDDUSB_CAP)") (class "Default")
      (node (ref "C114") (pin "1") (pinfunction "1_1") (pintype "passive"))
      (node (ref "C115") (pin "1") (pinfunction "1_1") (pintype "passive"))
      (node (ref "U3") (pin "F9") (pinfunction "VDDUSB_CAP_F9") (pintype "power_in"))
    )
    (net (code "241") (name "Net-(U3I-HDMI_DDCCEC)") (class "Default")
      (node (ref "R29") (pin "1") (pinfunction "1_1") (pintype "passive"))
      (node (ref "U3") (pin "K2") (pinfunction "HDMI_DDCCEC_K2") (pintype "bidirectional"))
    )
    (net (code "242") (name "Net-(U3I-HDMI_REF)") (class "Default")
      (node (ref "R31") (pin "1") (pinfunction "1_1") (pintype "passive"))
      (node (ref "U3") (pin "J1") (pinfunction "HDMI_REF_J1") (pintype "input"))
    )
    (net (code "243") (name "Net-(U3L-PCIE_REXT)") (class "Default")
      (node (ref "R32") (pin "1") (pinfunction "1_1") (pintype "passive"))
      (node (ref "U3") (pin "A2") (pinfunction "PCIE_REXT_A2") (pintype "input"))
    )
    (net (code "244") (name "Net-(U3L-PCIE_VPTX)") (class "Default")
      (node (ref "C124") (pin "1") (pinfunction "1_1") (pintype "passive"))
      (node (ref "L5") (pin "2") (pinfunction "2_2") (pintype "passive"))
      (node (ref "U3") (pin "G8") (pinfunction "PCIE_VPTX_G8") (pintype "power_in"))
    )
    (net (code "245") (name "P3V3-PERI") (class "Default")
      (node (ref "R11") (pin "1") (pinfunction "1_1") (pintype "passive"))
      (node (ref "R12") (pin "1") (pinfunction "1_1") (pintype "passive"))
      (node (ref "R14") (pin "1") (pinfunction "1_1") (pintype "passive"))
      (node (ref "R15") (pin "1") (pinfunction "1_1") (pintype "passive"))
      (node (ref "R16") (pin "1") (pinfunction "1_1") (pintype "passive"))
      (node (ref "R17") (pin "1") (pinfunction "1_1") (pintype "passive"))
      (node (ref "R18") (pin "1") (pinfunction "1_1") (pintype "passive"))
      (node (ref "R21") (pin "2") (pinfunction "2_2") (pintype "passive"))
      (node (ref "R22") (pin "2") (pinfunction "2_2") (pintype "passive"))
      (node (ref "R23") (pin "2") (pinfunction "2_2") (pintype "passive"))
      (node (ref "R26") (pin "2") (pinfunction "2_2") (pintype "passive"))
      (node (ref "R8") (pin "2") (pinfunction "2_2") (pintype "passive"))
      (node (ref "U14") (pin "4") (pinfunction "VCC_4") (pintype "passive"))
      (node (ref "U2") (pin "4") (pinfunction "VCC_4") (pintype "passive"))
      (node (ref "U4") (pin "5") (pinfunction "VCC_5") (pintype "passive"))
      (node (ref "U5") (pin "5") (pinfunction "VCC_5") (pintype "passive"))
      (node (ref "U6") (pin "5") (pinfunction "VCC_5") (pintype "passive"))
    )
    (net (code "246") (name "VDDHIGH-CAP") (class "Default")
      (node (ref "C110") (pin "1") (pinfunction "1_1") (pintype "passive"))
      (node (ref "C116") (pin "1") (pinfunction "1_1") (pintype "passive"))
      (node (ref "C123") (pin "1") (pinfunction "1_1") (pintype "passive"))
      (node (ref "C125") (pin "1") (pinfunction "1_1") (pintype "passive"))
      (node (ref "U3") (pin "G12") (pinfunction "SATA_VPH_G12") (pintype "power_in"))
      (node (ref "U3") (pin "G7") (pinfunction "PCIE_VPH_G7") (pintype "power_in"))
      (node (ref "U3") (pin "M7") (pinfunction "HDMI_VPH_M7") (pintype "power_in"))
      (node (ref "U3") (pin "V7") (pinfunction "NVCC_LVDS2P5_V7") (pintype "power_in"))
    )
    (net (code "247") (name "VDDSOC-CAP") (class "Default")
      (node (ref "C109") (pin "1") (pinfunction "1_1") (pintype "passive"))
      (node (ref "C113") (pin "1") (pinfunction "1_1") (pintype "passive"))
      (node (ref "C122") (pin "1") (pinfunction "1_1") (pintype "passive"))
      (node (ref "L5") (pin "1") (pinfunction "1_1") (pintype "passive"))
      (node (ref "U3") (pin "G13") (pinfunction "SATA_VP_G13") (pintype "power_in"))
      (node (ref "U3") (pin "H7") (pinfunction "PCIE_VP_H7") (pintype "power_in"))
      (node (ref "U3") (pin "L7") (pinfunction "HDMI_VP_L7") (pintype "power_in"))
    )
    (net (code "248") (name "unconnected-(U3A-EIM_A25-PadH19)") (class "Default")
      (node (ref "U3") (pin "H19") (pinfunction "EIM_A25_H19") (pintype "bidirectional"))
    )
    (net (code "249") (name "unconnected-(U3A-EIM_BCLK-PadN22)") (class "Default")
      (node (ref "U3") (pin "N22") (pinfunction "EIM_BCLK_N22") (pintype "bidirectional"))
    )
    (net (code "250") (name "unconnected-(U3A-EIM_CS0-PadH24)") (class "Default")
      (node (ref "U3") (pin "H24") (pinfunction "EIM_CS0_H24") (pintype "bidirectional"))
    )
    (net (code "251") (name "unconnected-(U3A-EIM_CS1-PadJ23)") (class "Default")
      (node (ref "U3") (pin "J23") (pinfunction "EIM_CS1_J23") (pintype "bidirectional"))
    )
    (net (code "252") (name "unconnected-(U3A-EIM_OE-PadJ24)") (class "Default")
      (node (ref "U3") (pin "J24") (pinfunction "EIM_OE_J24") (pintype "bidirectional"))
    )
    (net (code "253") (name "unconnected-(U3B-GPIO_16-PadR2)") (class "Default")
      (node (ref "U3") (pin "R2") (pinfunction "GPIO_16_R2") (pintype "bidirectional"))
    )
    (net (code "254") (name "unconnected-(U3B-KEY_COL2-PadW6)") (class "Default")
      (node (ref "U3") (pin "W6") (pinfunction "KEY_COL2_W6") (pintype "bidirectional"))
    )
    (net (code "255") (name "unconnected-(U3B-KEY_ROW2-PadW4)") (class "Default")
      (node (ref "U3") (pin "W4") (pinfunction "KEY_ROW2_W4") (pintype "bidirectional"))
    )
    (net (code "256") (name "unconnected-(U3B-MLB_CN-PadA11)") (class "Default")
      (node (ref "U3") (pin "A11") (pinfunction "MLB_CN_A11") (pintype "input+no_connect"))
    )
    (net (code "257") (name "unconnected-(U3B-MLB_CP-PadB11)") (class "Default")
      (node (ref "U3") (pin "B11") (pinfunction "MLB_CP_B11") (pintype "input+no_connect"))
    )
    (net (code "258") (name "unconnected-(U3B-MLB_DN-PadB10)") (class "Default")
      (node (ref "U3") (pin "B10") (pinfunction "MLB_DN_B10") (pintype "bidirectional"))
    )
    (net (code "259") (name "unconnected-(U3B-MLB_DP-PadA10)") (class "Default")
      (node (ref "U3") (pin "A10") (pinfunction "MLB_DP_A10") (pintype "bidirectional"))
    )
    (net (code "260") (name "unconnected-(U3B-MLB_SN-PadA9)") (class "Default")
      (node (ref "U3") (pin "A9") (pinfunction "MLB_SN_A9") (pintype "bidirectional"))
    )
    (net (code "261") (name "unconnected-(U3B-MLB_SP-PadB9)") (class "Default")
      (node (ref "U3") (pin "B9") (pinfunction "MLB_SP_B9") (pintype "bidirectional"))
    )
    (net (code "262") (name "unconnected-(U3B-NANDF_CLE-PadC15)") (class "Default")
      (node (ref "U3") (pin "C15") (pinfunction "NANDF_CLE_C15") (pintype "bidirectional"))
    )
    (net (code "263") (name "unconnected-(U3B-SD1_CLK-PadD20)") (class "Default")
      (node (ref "U3") (pin "D20") (pinfunction "SD1_CLK_D20") (pintype "bidirectional"))
    )
    (net (code "264") (name "unconnected-(U3B-SD1_CMD-PadB21)") (class "Default")
      (node (ref "U3") (pin "B21") (pinfunction "SD1_CMD_B21") (pintype "bidirectional"))
    )
    (net (code "265") (name "unconnected-(U3B-SD1_DAT0-PadA21)") (class "Default")
      (node (ref "U3") (pin "A21") (pinfunction "SD1_DAT0_A21") (pintype "bidirectional"))
    )
    (net (code "266") (name "unconnected-(U3B-~{NANDF_WP}-PadE15)") (class "Default")
      (node (ref "U3") (pin "E15") (pinfunction "~{NANDF_WP}_E15") (pintype "bidirectional"))
    )
    (net (code "267") (name "unconnected-(U3C-CLK2_N-PadC5)") (class "Default")
      (node (ref "U3") (pin "C5") (pinfunction "CLK2_N_C5") (pintype "bidirectional"))
    )
    (net (code "268") (name "unconnected-(U3C-CLK2_P-PadD5)") (class "Default")
      (node (ref "U3") (pin "D5") (pinfunction "CLK2_P_D5") (pintype "bidirectional"))
    )
    (net (code "269") (name "unconnected-(U3D-CSI_CLK0M-PadF4)") (class "Default")
      (node (ref "U3") (pin "F4") (pinfunction "CSI_CLK0M_F4") (pintype "input+no_connect"))
    )
    (net (code "270") (name "unconnected-(U3D-CSI_CLK0P-PadF3)") (class "Default")
      (node (ref "U3") (pin "F3") (pinfunction "CSI_CLK0P_F3") (pintype "input+no_connect"))
    )
    (net (code "271") (name "unconnected-(U3D-CSI_D0M-PadE4)") (class "Default")
      (node (ref "U3") (pin "E4") (pinfunction "CSI_D0M_E4") (pintype "input+no_connect"))
    )
    (net (code "272") (name "unconnected-(U3D-CSI_D0P-PadE3)") (class "Default")
      (node (ref "U3") (pin "E3") (pinfunction "CSI_D0P_E3") (pintype "input+no_connect"))
    )
    (net (code "273") (name "unconnected-(U3D-CSI_D1M-PadD1)") (class "Default")
      (node (ref "U3") (pin "D1") (pinfunction "CSI_D1M_D1") (pintype "input+no_connect"))
    )
    (net (code "274") (name "unconnected-(U3D-CSI_D1P-PadD2)") (class "Default")
      (node (ref "U3") (pin "D2") (pinfunction "CSI_D1P_D2") (pintype "input+no_connect"))
    )
    (net (code "275") (name "unconnected-(U3D-CSI_D2M-PadE1)") (class "Default")
      (node (ref "U3") (pin "E1") (pinfunction "CSI_D2M_E1") (pintype "input+no_connect"))
    )
    (net (code "276") (name "unconnected-(U3D-CSI_D2P-PadE2)") (class "Default")
      (node (ref "U3") (pin "E2") (pinfunction "CSI_D2P_E2") (pintype "input+no_connect"))
    )
    (net (code "277") (name "unconnected-(U3D-CSI_D3M-PadF2)") (class "Default")
      (node (ref "U3") (pin "F2") (pinfunction "CSI_D3M_F2") (pintype "input+no_connect"))
    )
    (net (code "278") (name "unconnected-(U3D-CSI_D3P-PadF1)") (class "Default")
      (node (ref "U3") (pin "F1") (pinfunction "CSI_D3P_F1") (pintype "input+no_connect"))
    )
    (net (code "279") (name "unconnected-(U3D-DI0_DISP_CLK-PadN19)") (class "Default")
      (node (ref "U3") (pin "N19") (pinfunction "DI0_DISP_CLK_N19") (pintype "bidirectional"))
    )
    (net (code "280") (name "unconnected-(U3D-DISP0_DAT9-PadT25)") (class "Default")
      (node (ref "U3") (pin "T25") (pinfunction "DISP0_DAT9_T25") (pintype "bidirectional"))
    )
    (net (code "281") (name "unconnected-(U3D-DISP0_DAT10-PadR21)") (class "Default")
      (node (ref "U3") (pin "R21") (pinfunction "DISP0_DAT10_R21") (pintype "bidirectional"))
    )
    (net (code "282") (name "unconnected-(U3D-DISP0_DAT11-PadT23)") (class "Default")
      (node (ref "U3") (pin "T23") (pinfunction "DISP0_DAT11_T23") (pintype "bidirectional"))
    )
    (net (code "283") (name "unconnected-(U3D-DISP0_DAT12-PadT24)") (class "Default")
      (node (ref "U3") (pin "T24") (pinfunction "DISP0_DAT12_T24") (pintype "bidirectional"))
    )
    (net (code "284") (name "unconnected-(U3D-DISP0_DAT13-PadR20)") (class "Default")
      (node (ref "U3") (pin "R20") (pinfunction "DISP0_DAT13_R20") (pintype "bidirectional"))
    )
    (net (code "285") (name "unconnected-(U3D-DISP0_DAT14-PadU25)") (class "Default")
      (node (ref "U3") (pin "U25") (pinfunction "DISP0_DAT14_U25") (pintype "bidirectional"))
    )
    (net (code "286") (name "unconnected-(U3D-DISP0_DAT15-PadT22)") (class "Default")
      (node (ref "U3") (pin "T22") (pinfunction "DISP0_DAT15_T22") (pintype "bidirectional"))
    )
    (net (code "287") (name "unconnected-(U3D-DSI_CLK0M-PadH3)") (class "Default")
      (node (ref "U3") (pin "H3") (pinfunction "DSI_CLK0M_H3") (pintype "output"))
    )
    (net (code "288") (name "unconnected-(U3D-DSI_CLK0P-PadH4)") (class "Default")
      (node (ref "U3") (pin "H4") (pinfunction "DSI_CLK0P_H4") (pintype "output"))
    )
    (net (code "289") (name "unconnected-(U3D-DSI_D0M-PadG2)") (class "Default")
      (node (ref "U3") (pin "G2") (pinfunction "DSI_D0M_G2") (pintype "output"))
    )
    (net (code "290") (name "unconnected-(U3D-DSI_D0P-PadG1)") (class "Default")
      (node (ref "U3") (pin "G1") (pinfunction "DSI_D0P_G1") (pintype "output"))
    )
    (net (code "291") (name "unconnected-(U3D-DSI_D1M-PadH2)") (class "Default")
      (node (ref "U3") (pin "H2") (pinfunction "DSI_D1M_H2") (pintype "output"))
    )
    (net (code "292") (name "unconnected-(U3D-DSI_D1P-PadH1)") (class "Default")
      (node (ref "U3") (pin "H1") (pinfunction "DSI_D1P_H1") (pintype "output"))
    )
    (net (code "293") (name "unconnected-(U3G-~{USB_OTG_CHD}-PadB8)") (class "Default")
      (node (ref "U3") (pin "B8") (pinfunction "~{USB_OTG_CHD}_B8") (pintype "output"))
    )
    (net (code "294") (name "unconnected-(U3H-LVDS1_CLK_N-PadY3)") (class "Default")
      (node (ref "U3") (pin "Y3") (pinfunction "LVDS1_CLK_N_Y3") (pintype "output"))
    )
    (net (code "295") (name "unconnected-(U3H-LVDS1_CLK_P-PadY4)") (class "Default")
      (node (ref "U3") (pin "Y4") (pinfunction "LVDS1_CLK_P_Y4") (pintype "output"))
    )
    (net (code "296") (name "unconnected-(U3H-LVDS1_TX0_N-PadY1)") (class "Default")
      (node (ref "U3") (pin "Y1") (pinfunction "LVDS1_TX0_N_Y1") (pintype "output"))
    )
    (net (code "297") (name "unconnected-(U3H-LVDS1_TX0_P-PadY2)") (class "Default")
      (node (ref "U3") (pin "Y2") (pinfunction "LVDS1_TX0_P_Y2") (pintype "output"))
    )
    (net (code "298") (name "unconnected-(U3H-LVDS1_TX1_N-PadAA2)") (class "Default")
      (node (ref "U3") (pin "AA2") (pinfunction "LVDS1_TX1_N_AA2") (pintype "output"))
    )
    (net (code "299") (name "unconnected-(U3H-LVDS1_TX1_P-PadAA1)") (class "Default")
      (node (ref "U3") (pin "AA1") (pinfunction "LVDS1_TX1_P_AA1") (pintype "output"))
    )
    (net (code "300") (name "unconnected-(U3H-LVDS1_TX2_N-PadAB1)") (class "Default")
      (node (ref "U3") (pin "AB1") (pinfunction "LVDS1_TX2_N_AB1") (pintype "output"))
    )
    (net (code "301") (name "unconnected-(U3H-LVDS1_TX2_P-PadAB2)") (class "Default")
      (node (ref "U3") (pin "AB2") (pinfunction "LVDS1_TX2_P_AB2") (pintype "output"))
    )
    (net (code "302") (name "unconnected-(U3H-LVDS1_TX3_N-PadAA3)") (class "Default")
      (node (ref "U3") (pin "AA3") (pinfunction "LVDS1_TX3_N_AA3") (pintype "output"))
    )
    (net (code "303") (name "unconnected-(U3H-LVDS1_TX3_P-PadAA4)") (class "Default")
      (node (ref "U3") (pin "AA4") (pinfunction "LVDS1_TX3_P_AA4") (pintype "output"))
    )
    (net (code "304") (name "unconnected-(Y1-Pad2)") (class "Default")
      (node (ref "Y1") (pin "2") (pinfunction "2_2") (pintype "passive"))
    )
    (net (code "305") (name "unconnected-(Y1-Pad4)") (class "Default")
      (node (ref "Y1") (pin "4") (pinfunction "4_4") (pintype "passive"))
    )
  )
)
